# untitled.net
KiCad netlist of a schematic drawn in EAGLE
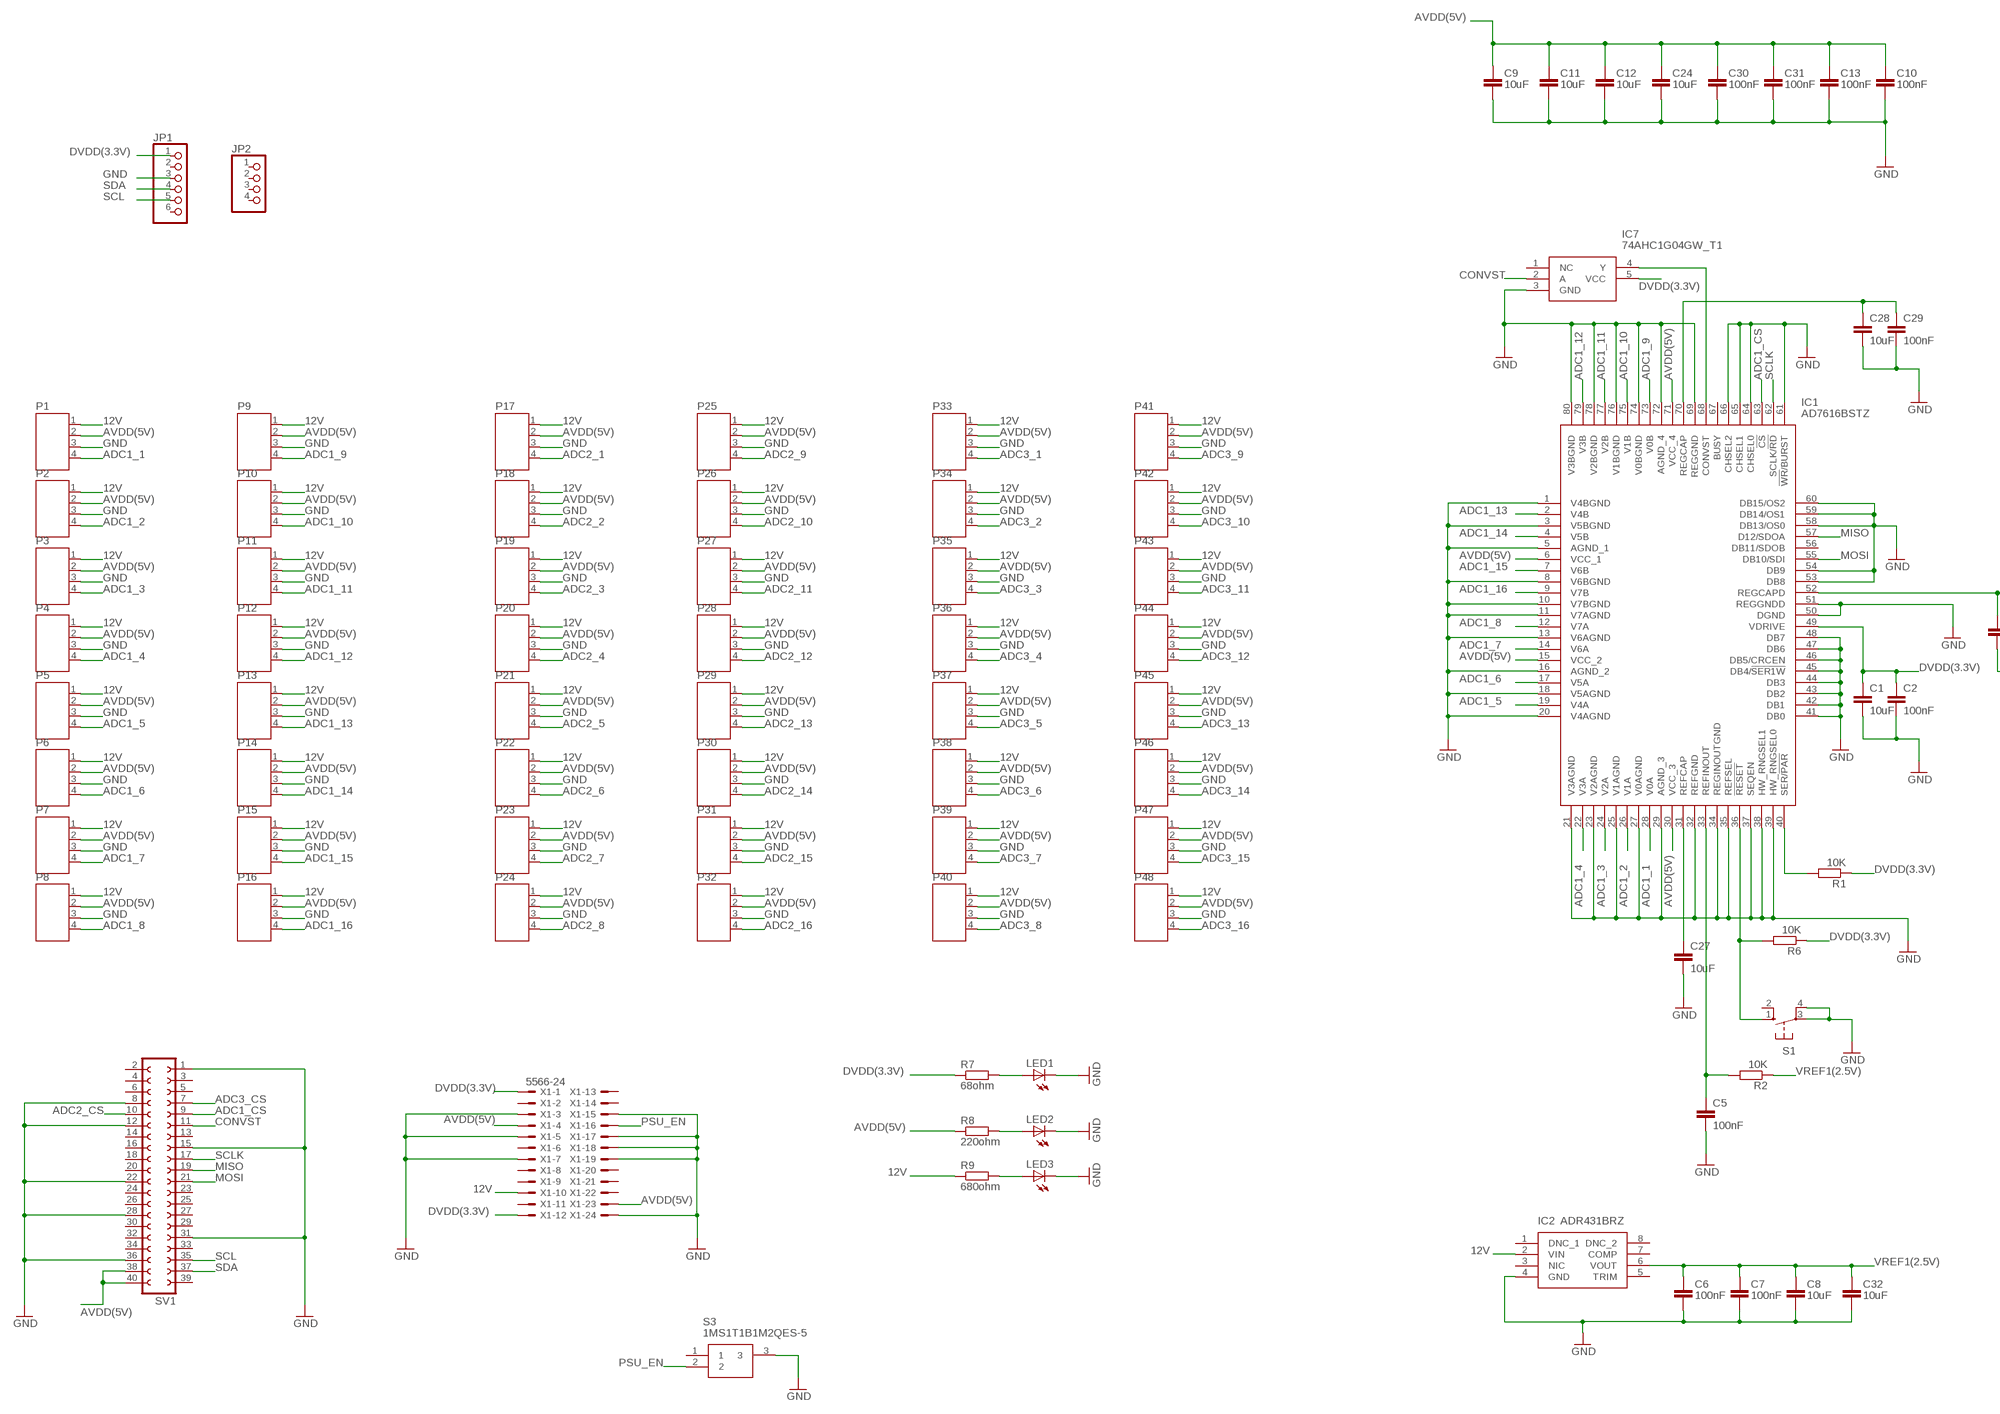
[diagram p0: schematic, sheet 1, part 1 of 2]
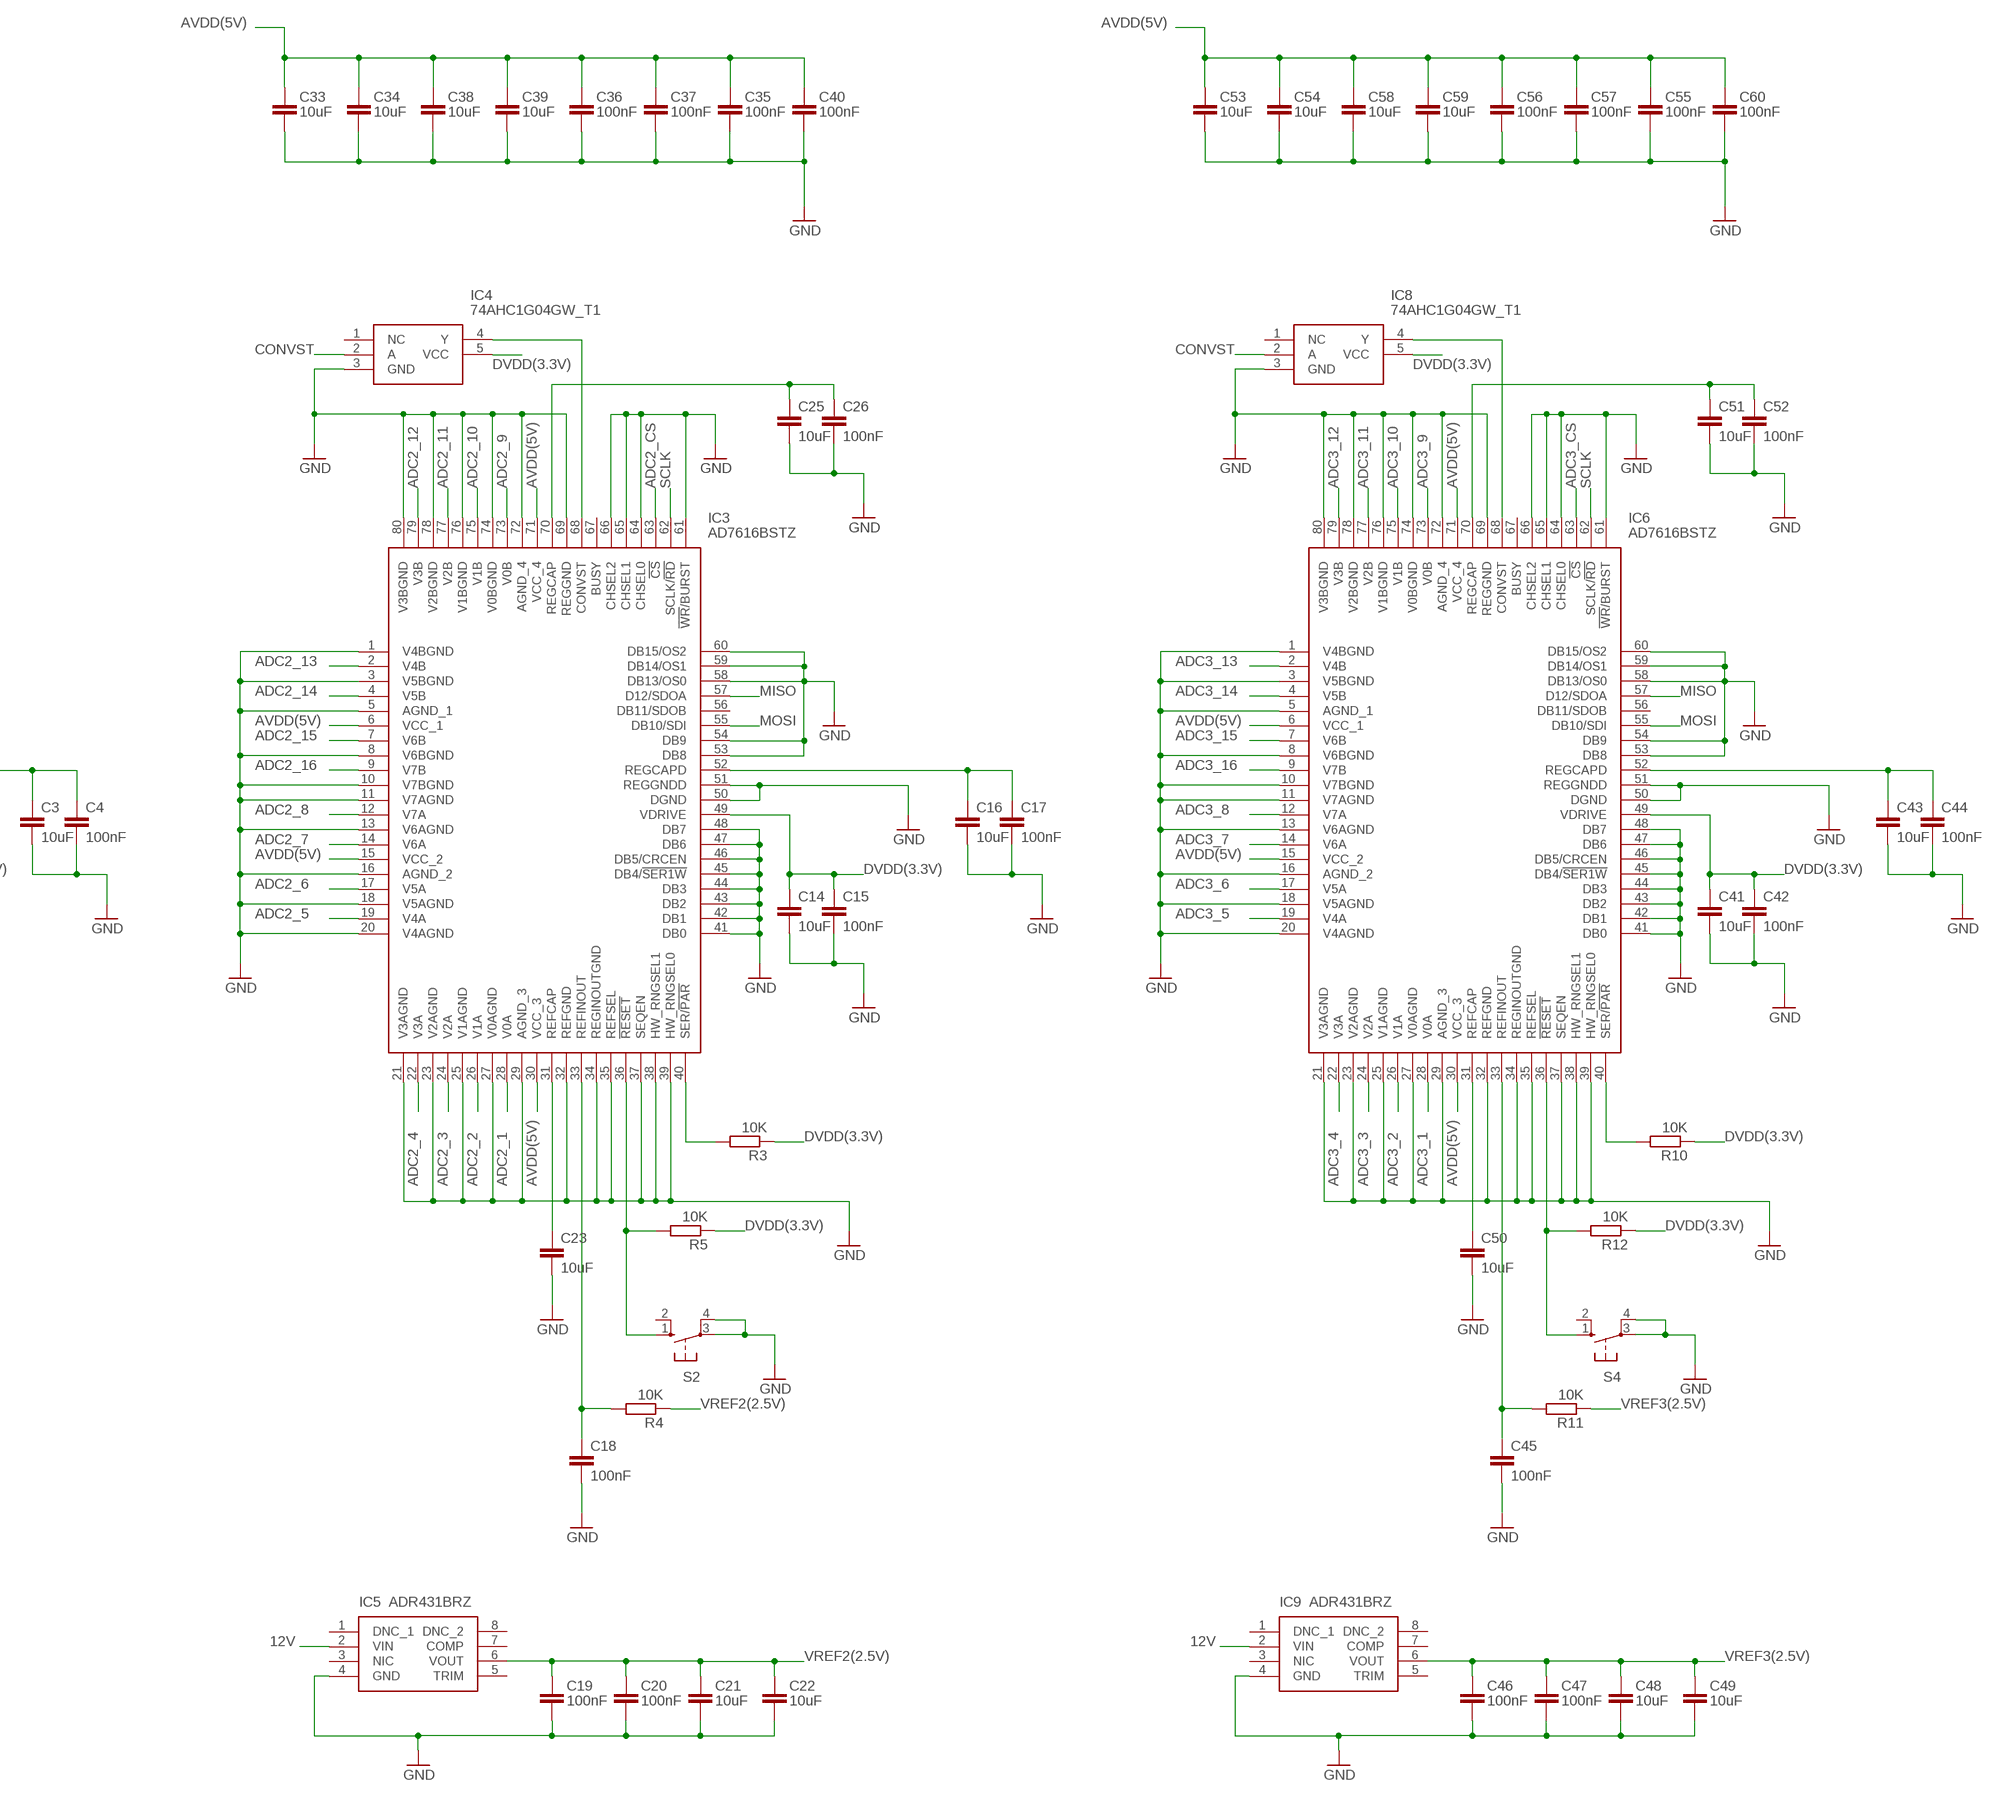
[diagram p1: schematic, sheet 1, part 2 of 2]

(export (version "E")
  (design (tool "Eeschema 10.0.6"))
  (components
    (comp (ref "C1")
      (value "10uF")
      (footprint "eagle-import:C1206")
      (libsource (lib "eagle-import") (part "C-EUC1206"))
    )
    (comp (ref "C2")
      (value "100nF")
      (footprint "eagle-import:C0603")
      (libsource (lib "eagle-import") (part "C-EUC0603"))
    )
    (comp (ref "C3")
      (value "10uF")
      (footprint "eagle-import:C1206")
      (libsource (lib "eagle-import") (part "C-EUC1206"))
    )
    (comp (ref "C4")
      (value "100nF")
      (footprint "eagle-import:C0603")
      (libsource (lib "eagle-import") (part "C-EUC0603"))
    )
    (comp (ref "C5")
      (value "100nF")
      (footprint "eagle-import:C0603")
      (libsource (lib "eagle-import") (part "C-EUC0603"))
    )
    (comp (ref "C6")
      (value "100nF")
      (footprint "eagle-import:C0603")
      (libsource (lib "eagle-import") (part "C-EUC0603"))
    )
    (comp (ref "C7")
      (value "100nF")
      (footprint "eagle-import:C0603")
      (libsource (lib "eagle-import") (part "C-EUC0603"))
    )
    (comp (ref "C8")
      (value "10uF")
      (footprint "eagle-import:C1206")
      (libsource (lib "eagle-import") (part "C-EUC1206"))
    )
    (comp (ref "C9")
      (value "10uF")
      (footprint "eagle-import:C1206")
      (libsource (lib "eagle-import") (part "C-EUC1206"))
    )
    (comp (ref "C10")
      (value "100nF")
      (footprint "eagle-import:C0603")
      (libsource (lib "eagle-import") (part "C-EUC0603"))
    )
    (comp (ref "C11")
      (value "10uF")
      (footprint "eagle-import:C1206")
      (libsource (lib "eagle-import") (part "C-EUC1206"))
    )
    (comp (ref "C12")
      (value "10uF")
      (footprint "eagle-import:C1206")
      (libsource (lib "eagle-import") (part "C-EUC1206"))
    )
    (comp (ref "C13")
      (value "100nF")
      (footprint "eagle-import:C0603")
      (libsource (lib "eagle-import") (part "C-EUC0603"))
    )
    (comp (ref "C14")
      (value "10uF")
      (footprint "eagle-import:C1206")
      (libsource (lib "eagle-import") (part "C-EUC1206"))
    )
    (comp (ref "C15")
      (value "100nF")
      (footprint "eagle-import:C0603")
      (libsource (lib "eagle-import") (part "C-EUC0603"))
    )
    (comp (ref "C16")
      (value "10uF")
      (footprint "eagle-import:C1206")
      (libsource (lib "eagle-import") (part "C-EUC1206"))
    )
    (comp (ref "C17")
      (value "100nF")
      (footprint "eagle-import:C0603")
      (libsource (lib "eagle-import") (part "C-EUC0603"))
    )
    (comp (ref "C18")
      (value "100nF")
      (footprint "eagle-import:C0603")
      (libsource (lib "eagle-import") (part "C-EUC0603"))
    )
    (comp (ref "C19")
      (value "100nF")
      (footprint "eagle-import:C0603")
      (libsource (lib "eagle-import") (part "C-EUC0603"))
    )
    (comp (ref "C20")
      (value "100nF")
      (footprint "eagle-import:C0603")
      (libsource (lib "eagle-import") (part "C-EUC0603"))
    )
    (comp (ref "C21")
      (value "10uF")
      (footprint "eagle-import:C1206")
      (libsource (lib "eagle-import") (part "C-EUC1206"))
    )
    (comp (ref "C22")
      (value "10uF")
      (footprint "eagle-import:C1206")
      (libsource (lib "eagle-import") (part "C-EUC1206"))
    )
    (comp (ref "C23")
      (value "10uF")
      (footprint "eagle-import:C1206")
      (libsource (lib "eagle-import") (part "C-EUC1206"))
    )
    (comp (ref "C24")
      (value "10uF")
      (footprint "eagle-import:C1206")
      (libsource (lib "eagle-import") (part "C-EUC1206"))
    )
    (comp (ref "C25")
      (value "10uF")
      (footprint "eagle-import:C1206")
      (libsource (lib "eagle-import") (part "C-EUC1206"))
    )
    (comp (ref "C26")
      (value "100nF")
      (footprint "eagle-import:C0603")
      (libsource (lib "eagle-import") (part "C-EUC0603"))
    )
    (comp (ref "C27")
      (value "10uF")
      (footprint "eagle-import:C1206")
      (libsource (lib "eagle-import") (part "C-EUC1206"))
    )
    (comp (ref "C28")
      (value "10uF")
      (footprint "eagle-import:C1206")
      (libsource (lib "eagle-import") (part "C-EUC1206"))
    )
    (comp (ref "C29")
      (value "100nF")
      (footprint "eagle-import:C0603")
      (libsource (lib "eagle-import") (part "C-EUC0603"))
    )
    (comp (ref "C30")
      (value "100nF")
      (footprint "eagle-import:C0603")
      (libsource (lib "eagle-import") (part "C-EUC0603"))
    )
    (comp (ref "C31")
      (value "100nF")
      (footprint "eagle-import:C0603")
      (libsource (lib "eagle-import") (part "C-EUC0603"))
    )
    (comp (ref "C32")
      (value "10uF")
      (footprint "eagle-import:C1206")
      (libsource (lib "eagle-import") (part "C-EUC1206"))
    )
    (comp (ref "C33")
      (value "10uF")
      (footprint "eagle-import:C1206")
      (libsource (lib "eagle-import") (part "C-EUC1206"))
    )
    (comp (ref "C34")
      (value "10uF")
      (footprint "eagle-import:C1206")
      (libsource (lib "eagle-import") (part "C-EUC1206"))
    )
    (comp (ref "C35")
      (value "100nF")
      (footprint "eagle-import:C0603")
      (libsource (lib "eagle-import") (part "C-EUC0603"))
    )
    (comp (ref "C36")
      (value "100nF")
      (footprint "eagle-import:C0603")
      (libsource (lib "eagle-import") (part "C-EUC0603"))
    )
    (comp (ref "C37")
      (value "100nF")
      (footprint "eagle-import:C0603")
      (libsource (lib "eagle-import") (part "C-EUC0603"))
    )
    (comp (ref "C38")
      (value "10uF")
      (footprint "eagle-import:C1206")
      (libsource (lib "eagle-import") (part "C-EUC1206"))
    )
    (comp (ref "C39")
      (value "10uF")
      (footprint "eagle-import:C1206")
      (libsource (lib "eagle-import") (part "C-EUC1206"))
    )
    (comp (ref "C40")
      (value "100nF")
      (footprint "eagle-import:C0603")
      (libsource (lib "eagle-import") (part "C-EUC0603"))
    )
    (comp (ref "C41")
      (value "10uF")
      (footprint "eagle-import:C1206")
      (libsource (lib "eagle-import") (part "C-EUC1206"))
    )
    (comp (ref "C42")
      (value "100nF")
      (footprint "eagle-import:C0603")
      (libsource (lib "eagle-import") (part "C-EUC0603"))
    )
    (comp (ref "C43")
      (value "10uF")
      (footprint "eagle-import:C1206")
      (libsource (lib "eagle-import") (part "C-EUC1206"))
    )
    (comp (ref "C44")
      (value "100nF")
      (footprint "eagle-import:C0603")
      (libsource (lib "eagle-import") (part "C-EUC0603"))
    )
    (comp (ref "C45")
      (value "100nF")
      (footprint "eagle-import:C0603")
      (libsource (lib "eagle-import") (part "C-EUC0603"))
    )
    (comp (ref "C46")
      (value "100nF")
      (footprint "eagle-import:C0603")
      (libsource (lib "eagle-import") (part "C-EUC0603"))
    )
    (comp (ref "C47")
      (value "100nF")
      (footprint "eagle-import:C0603")
      (libsource (lib "eagle-import") (part "C-EUC0603"))
    )
    (comp (ref "C48")
      (value "10uF")
      (footprint "eagle-import:C1206")
      (libsource (lib "eagle-import") (part "C-EUC1206"))
    )
    (comp (ref "C49")
      (value "10uF")
      (footprint "eagle-import:C1206")
      (libsource (lib "eagle-import") (part "C-EUC1206"))
    )
    (comp (ref "C50")
      (value "10uF")
      (footprint "eagle-import:C1206")
      (libsource (lib "eagle-import") (part "C-EUC1206"))
    )
    (comp (ref "C51")
      (value "10uF")
      (footprint "eagle-import:C1206")
      (libsource (lib "eagle-import") (part "C-EUC1206"))
    )
    (comp (ref "C52")
      (value "100nF")
      (footprint "eagle-import:C0603")
      (libsource (lib "eagle-import") (part "C-EUC0603"))
    )
    (comp (ref "C53")
      (value "10uF")
      (footprint "eagle-import:C1206")
      (libsource (lib "eagle-import") (part "C-EUC1206"))
    )
    (comp (ref "C54")
      (value "10uF")
      (footprint "eagle-import:C1206")
      (libsource (lib "eagle-import") (part "C-EUC1206"))
    )
    (comp (ref "C55")
      (value "100nF")
      (footprint "eagle-import:C0603")
      (libsource (lib "eagle-import") (part "C-EUC0603"))
    )
    (comp (ref "C56")
      (value "100nF")
      (footprint "eagle-import:C0603")
      (libsource (lib "eagle-import") (part "C-EUC0603"))
    )
    (comp (ref "C57")
      (value "100nF")
      (footprint "eagle-import:C0603")
      (libsource (lib "eagle-import") (part "C-EUC0603"))
    )
    (comp (ref "C58")
      (value "10uF")
      (footprint "eagle-import:C1206")
      (libsource (lib "eagle-import") (part "C-EUC1206"))
    )
    (comp (ref "C59")
      (value "10uF")
      (footprint "eagle-import:C1206")
      (libsource (lib "eagle-import") (part "C-EUC1206"))
    )
    (comp (ref "C60")
      (value "100nF")
      (footprint "eagle-import:C0603")
      (libsource (lib "eagle-import") (part "C-EUC0603"))
    )
    (comp (ref "IC1")
      (value "AD7616BSTZ")
      (footprint "eagle-import:QFP65P1600X1600X160-80N")
      (fields (field (name "MOUSER_PART_NUMBER") "584-AD7616BSTZ") (field (name "RS_PART_NUMBER") "1311218P"))
      (libsource (lib "eagle-import") (part "AD7616BSTZ"))
    )
    (comp (ref "IC2")
      (value "ADR431BRZ")
      (footprint "eagle-import:SOIC127P600X175-8N")
      (fields (field (name "MOUSER_PART_NUMBER") "584-ADR431BRZ") (field (name "RS_PART_NUMBER") "6977745P"))
      (libsource (lib "eagle-import") (part "ADR431BRZ"))
    )
    (comp (ref "IC3")
      (value "AD7616BSTZ")
      (footprint "eagle-import:QFP65P1600X1600X160-80N")
      (fields (field (name "MOUSER_PART_NUMBER") "584-AD7616BSTZ") (field (name "RS_PART_NUMBER") "1311218P"))
      (libsource (lib "eagle-import") (part "AD7616BSTZ"))
    )
    (comp (ref "IC4")
      (value "74AHC1G04GW_T1")
      (footprint "eagle-import:SOT65P212X110-5N")
      (fields (field (name "MANUFACTURER_PART_NUMBER") "74AHC1G04GW/T1"))
      (libsource (lib "eagle-import") (part "74AHC1G04GW_T1"))
    )
    (comp (ref "IC5")
      (value "ADR431BRZ")
      (footprint "eagle-import:SOIC127P600X175-8N")
      (fields (field (name "MOUSER_PART_NUMBER") "584-ADR431BRZ") (field (name "RS_PART_NUMBER") "6977745P"))
      (libsource (lib "eagle-import") (part "ADR431BRZ"))
    )
    (comp (ref "IC6")
      (value "AD7616BSTZ")
      (footprint "eagle-import:QFP65P1600X1600X160-80N")
      (fields (field (name "MOUSER_PART_NUMBER") "584-AD7616BSTZ") (field (name "RS_PART_NUMBER") "1311218P"))
      (libsource (lib "eagle-import") (part "AD7616BSTZ"))
    )
    (comp (ref "IC7")
      (value "74AHC1G04GW_T1")
      (footprint "eagle-import:SOT65P212X110-5N")
      (fields (field (name "MANUFACTURER_PART_NUMBER") "74AHC1G04GW/T1"))
      (libsource (lib "eagle-import") (part "74AHC1G04GW_T1"))
    )
    (comp (ref "IC8")
      (value "74AHC1G04GW_T1")
      (footprint "eagle-import:SOT65P212X110-5N")
      (fields (field (name "MANUFACTURER_PART_NUMBER") "74AHC1G04GW/T1"))
      (libsource (lib "eagle-import") (part "74AHC1G04GW_T1"))
    )
    (comp (ref "IC9")
      (value "ADR431BRZ")
      (footprint "eagle-import:SOIC127P600X175-8N")
      (fields (field (name "MOUSER_PART_NUMBER") "584-ADR431BRZ") (field (name "RS_PART_NUMBER") "6977745P"))
      (libsource (lib "eagle-import") (part "ADR431BRZ"))
    )
    (comp (ref "JP1")
      (value "PINHD-1X6")
      (footprint "eagle-import:1X06")
      (libsource (lib "eagle-import") (part "PINHD-1X6"))
    )
    (comp (ref "JP2")
      (value "PINHD-1X4")
      (footprint "eagle-import:1X04")
      (libsource (lib "eagle-import") (part "PINHD-1X4"))
    )
    (comp (ref "LED1")
      (value "LEDCHIPLED_0603")
      (footprint "eagle-import:CHIPLED_0603")
      (libsource (lib "eagle-import") (part "LEDCHIPLED_0603"))
    )
    (comp (ref "LED2")
      (value "LEDCHIPLED_0603")
      (footprint "eagle-import:CHIPLED_0603")
      (libsource (lib "eagle-import") (part "LEDCHIPLED_0603"))
    )
    (comp (ref "LED3")
      (value "LEDCHIPLED_0603")
      (footprint "eagle-import:CHIPLED_0603")
      (libsource (lib "eagle-import") (part "LEDCHIPLED_0603"))
    )
    (comp (ref "P1")
      (value "JST-PH4")
      (footprint "eagle-import:JST-PH4")
      (libsource (lib "eagle-import") (part "JST-PH4"))
    )
    (comp (ref "P2")
      (value "JST-PH4")
      (footprint "eagle-import:JST-PH4")
      (libsource (lib "eagle-import") (part "JST-PH4"))
    )
    (comp (ref "P3")
      (value "JST-PH4")
      (footprint "eagle-import:JST-PH4")
      (libsource (lib "eagle-import") (part "JST-PH4"))
    )
    (comp (ref "P4")
      (value "JST-PH4")
      (footprint "eagle-import:JST-PH4")
      (libsource (lib "eagle-import") (part "JST-PH4"))
    )
    (comp (ref "P5")
      (value "JST-PH4")
      (footprint "eagle-import:JST-PH4")
      (libsource (lib "eagle-import") (part "JST-PH4"))
    )
    (comp (ref "P6")
      (value "JST-PH4")
      (footprint "eagle-import:JST-PH4")
      (libsource (lib "eagle-import") (part "JST-PH4"))
    )
    (comp (ref "P7")
      (value "JST-PH4")
      (footprint "eagle-import:JST-PH4")
      (libsource (lib "eagle-import") (part "JST-PH4"))
    )
    (comp (ref "P8")
      (value "JST-PH4")
      (footprint "eagle-import:JST-PH4")
      (libsource (lib "eagle-import") (part "JST-PH4"))
    )
    (comp (ref "P9")
      (value "JST-PH4")
      (footprint "eagle-import:JST-PH4")
      (libsource (lib "eagle-import") (part "JST-PH4"))
    )
    (comp (ref "P10")
      (value "JST-PH4")
      (footprint "eagle-import:JST-PH4")
      (libsource (lib "eagle-import") (part "JST-PH4"))
    )
    (comp (ref "P11")
      (value "JST-PH4")
      (footprint "eagle-import:JST-PH4")
      (libsource (lib "eagle-import") (part "JST-PH4"))
    )
    (comp (ref "P12")
      (value "JST-PH4")
      (footprint "eagle-import:JST-PH4")
      (libsource (lib "eagle-import") (part "JST-PH4"))
    )
    (comp (ref "P13")
      (value "JST-PH4")
      (footprint "eagle-import:JST-PH4")
      (libsource (lib "eagle-import") (part "JST-PH4"))
    )
    (comp (ref "P14")
      (value "JST-PH4")
      (footprint "eagle-import:JST-PH4")
      (libsource (lib "eagle-import") (part "JST-PH4"))
    )
    (comp (ref "P15")
      (value "JST-PH4")
      (footprint "eagle-import:JST-PH4")
      (libsource (lib "eagle-import") (part "JST-PH4"))
    )
    (comp (ref "P16")
      (value "JST-PH4")
      (footprint "eagle-import:JST-PH4")
      (libsource (lib "eagle-import") (part "JST-PH4"))
    )
    (comp (ref "P17")
      (value "JST-PH4")
      (footprint "eagle-import:JST-PH4")
      (libsource (lib "eagle-import") (part "JST-PH4"))
    )
    (comp (ref "P18")
      (value "JST-PH4")
      (footprint "eagle-import:JST-PH4")
      (libsource (lib "eagle-import") (part "JST-PH4"))
    )
    (comp (ref "P19")
      (value "JST-PH4")
      (footprint "eagle-import:JST-PH4")
      (libsource (lib "eagle-import") (part "JST-PH4"))
    )
    (comp (ref "P20")
      (value "JST-PH4")
      (footprint "eagle-import:JST-PH4")
      (libsource (lib "eagle-import") (part "JST-PH4"))
    )
    (comp (ref "P21")
      (value "JST-PH4")
      (footprint "eagle-import:JST-PH4")
      (libsource (lib "eagle-import") (part "JST-PH4"))
    )
    (comp (ref "P22")
      (value "JST-PH4")
      (footprint "eagle-import:JST-PH4")
      (libsource (lib "eagle-import") (part "JST-PH4"))
    )
    (comp (ref "P23")
      (value "JST-PH4")
      (footprint "eagle-import:JST-PH4")
      (libsource (lib "eagle-import") (part "JST-PH4"))
    )
    (comp (ref "P24")
      (value "JST-PH4")
      (footprint "eagle-import:JST-PH4")
      (libsource (lib "eagle-import") (part "JST-PH4"))
    )
    (comp (ref "P25")
      (value "JST-PH4")
      (footprint "eagle-import:JST-PH4")
      (libsource (lib "eagle-import") (part "JST-PH4"))
    )
    (comp (ref "P26")
      (value "JST-PH4")
      (footprint "eagle-import:JST-PH4")
      (libsource (lib "eagle-import") (part "JST-PH4"))
    )
    (comp (ref "P27")
      (value "JST-PH4")
      (footprint "eagle-import:JST-PH4")
      (libsource (lib "eagle-import") (part "JST-PH4"))
    )
    (comp (ref "P28")
      (value "JST-PH4")
      (footprint "eagle-import:JST-PH4")
      (libsource (lib "eagle-import") (part "JST-PH4"))
    )
    (comp (ref "P29")
      (value "JST-PH4")
      (footprint "eagle-import:JST-PH4")
      (libsource (lib "eagle-import") (part "JST-PH4"))
    )
    (comp (ref "P30")
      (value "JST-PH4")
      (footprint "eagle-import:JST-PH4")
      (libsource (lib "eagle-import") (part "JST-PH4"))
    )
    (comp (ref "P31")
      (value "JST-PH4")
      (footprint "eagle-import:JST-PH4")
      (libsource (lib "eagle-import") (part "JST-PH4"))
    )
    (comp (ref "P32")
      (value "JST-PH4")
      (footprint "eagle-import:JST-PH4")
      (libsource (lib "eagle-import") (part "JST-PH4"))
    )
    (comp (ref "P33")
      (value "JST-PH4")
      (footprint "eagle-import:JST-PH4")
      (libsource (lib "eagle-import") (part "JST-PH4"))
    )
    (comp (ref "P34")
      (value "JST-PH4")
      (footprint "eagle-import:JST-PH4")
      (libsource (lib "eagle-import") (part "JST-PH4"))
    )
    (comp (ref "P35")
      (value "JST-PH4")
      (footprint "eagle-import:JST-PH4")
      (libsource (lib "eagle-import") (part "JST-PH4"))
    )
    (comp (ref "P36")
      (value "JST-PH4")
      (footprint "eagle-import:JST-PH4")
      (libsource (lib "eagle-import") (part "JST-PH4"))
    )
    (comp (ref "P37")
      (value "JST-PH4")
      (footprint "eagle-import:JST-PH4")
      (libsource (lib "eagle-import") (part "JST-PH4"))
    )
    (comp (ref "P38")
      (value "JST-PH4")
      (footprint "eagle-import:JST-PH4")
      (libsource (lib "eagle-import") (part "JST-PH4"))
    )
    (comp (ref "P39")
      (value "JST-PH4")
      (footprint "eagle-import:JST-PH4")
      (libsource (lib "eagle-import") (part "JST-PH4"))
    )
    (comp (ref "P40")
      (value "JST-PH4")
      (footprint "eagle-import:JST-PH4")
      (libsource (lib "eagle-import") (part "JST-PH4"))
    )
    (comp (ref "P41")
      (value "JST-PH4")
      (footprint "eagle-import:JST-PH4")
      (libsource (lib "eagle-import") (part "JST-PH4"))
    )
    (comp (ref "P42")
      (value "JST-PH4")
      (footprint "eagle-import:JST-PH4")
      (libsource (lib "eagle-import") (part "JST-PH4"))
    )
    (comp (ref "P43")
      (value "JST-PH4")
      (footprint "eagle-import:JST-PH4")
      (libsource (lib "eagle-import") (part "JST-PH4"))
    )
    (comp (ref "P44")
      (value "JST-PH4")
      (footprint "eagle-import:JST-PH4")
      (libsource (lib "eagle-import") (part "JST-PH4"))
    )
    (comp (ref "P45")
      (value "JST-PH4")
      (footprint "eagle-import:JST-PH4")
      (libsource (lib "eagle-import") (part "JST-PH4"))
    )
    (comp (ref "P46")
      (value "JST-PH4")
      (footprint "eagle-import:JST-PH4")
      (libsource (lib "eagle-import") (part "JST-PH4"))
    )
    (comp (ref "P47")
      (value "JST-PH4")
      (footprint "eagle-import:JST-PH4")
      (libsource (lib "eagle-import") (part "JST-PH4"))
    )
    (comp (ref "P48")
      (value "JST-PH4")
      (footprint "eagle-import:JST-PH4")
      (libsource (lib "eagle-import") (part "JST-PH4"))
    )
    (comp (ref "R1")
      (value "10K")
      (footprint "eagle-import:R0603")
      (libsource (lib "eagle-import") (part "R-EU_R0603"))
    )
    (comp (ref "R2")
      (value "10K")
      (footprint "eagle-import:R0603")
      (libsource (lib "eagle-import") (part "R-EU_R0603"))
    )
    (comp (ref "R3")
      (value "10K")
      (footprint "eagle-import:R0603")
      (libsource (lib "eagle-import") (part "R-EU_R0603"))
    )
    (comp (ref "R4")
      (value "10K")
      (footprint "eagle-import:R0603")
      (libsource (lib "eagle-import") (part "R-EU_R0603"))
    )
    (comp (ref "R5")
      (value "10K")
      (footprint "eagle-import:R0603")
      (libsource (lib "eagle-import") (part "R-EU_R0603"))
    )
    (comp (ref "R6")
      (value "10K")
      (footprint "eagle-import:R0603")
      (libsource (lib "eagle-import") (part "R-EU_R0603"))
    )
    (comp (ref "R7")
      (value "68ohm")
      (footprint "eagle-import:R0805")
      (libsource (lib "eagle-import") (part "R-EU_R0805"))
    )
    (comp (ref "R8")
      (value "220ohm")
      (footprint "eagle-import:R0805")
      (libsource (lib "eagle-import") (part "R-EU_R0805"))
    )
    (comp (ref "R9")
      (value "680ohm")
      (footprint "eagle-import:R0805")
      (libsource (lib "eagle-import") (part "R-EU_R0805"))
    )
    (comp (ref "R10")
      (value "10K")
      (footprint "eagle-import:R0603")
      (libsource (lib "eagle-import") (part "R-EU_R0603"))
    )
    (comp (ref "R11")
      (value "10K")
      (footprint "eagle-import:R0603")
      (libsource (lib "eagle-import") (part "R-EU_R0603"))
    )
    (comp (ref "R12")
      (value "10K")
      (footprint "eagle-import:R0603")
      (libsource (lib "eagle-import") (part "R-EU_R0603"))
    )
    (comp (ref "S1")
      (value "10-XX")
      (footprint "eagle-import:B3F-10XX")
      (fields (field (name "MPN") "B3F-1000"))
      (libsource (lib "eagle-import") (part "10-XX"))
    )
    (comp (ref "S2")
      (value "10-XX")
      (footprint "eagle-import:B3F-10XX")
      (fields (field (name "MPN") "B3F-1000"))
      (libsource (lib "eagle-import") (part "10-XX"))
    )
    (comp (ref "S3")
      (value "1MS1T1B1M2QES-5")
      (footprint "eagle-import:1MS1T1B1M2QES-5")
      (fields (field (name "RS_PART_NUMBER") "7347066"))
      (libsource (lib "eagle-import") (part "1MS1T1B1M2QES-5"))
    )
    (comp (ref "S4")
      (value "10-XX")
      (footprint "eagle-import:B3F-10XX")
      (fields (field (name "MPN") "B3F-1000"))
      (libsource (lib "eagle-import") (part "10-XX"))
    )
    (comp (ref "SV1")
      (value "FE20-2")
      (footprint "eagle-import:FE20-2")
      (libsource (lib "eagle-import") (part "FE20-2"))
    )
    (comp (ref "X1")
      (value "5566-24")
      (footprint "eagle-import:5566-24")
      (fields (field (name "MF") "MOLEX"))
      (libsource (lib "eagle-import") (part "5566-24"))
    )
  )
  (nets
    (net (code "1") (name "/12V") (class "Default")
      (node (ref "IC2") (pin "2") (pinfunction "VIN_2") (pintype "bidirectional"))
      (node (ref "IC5") (pin "2") (pinfunction "VIN_2") (pintype "bidirectional"))
      (node (ref "IC9") (pin "2") (pinfunction "VIN_2") (pintype "bidirectional"))
      (node (ref "P1") (pin "1") (pinfunction "1_1") (pintype "passive"))
      (node (ref "P10") (pin "1") (pinfunction "1_1") (pintype "passive"))
      (node (ref "P11") (pin "1") (pinfunction "1_1") (pintype "passive"))
      (node (ref "P12") (pin "1") (pinfunction "1_1") (pintype "passive"))
      (node (ref "P13") (pin "1") (pinfunction "1_1") (pintype "passive"))
      (node (ref "P14") (pin "1") (pinfunction "1_1") (pintype "passive"))
      (node (ref "P15") (pin "1") (pinfunction "1_1") (pintype "passive"))
      (node (ref "P16") (pin "1") (pinfunction "1_1") (pintype "passive"))
      (node (ref "P17") (pin "1") (pinfunction "1_1") (pintype "passive"))
      (node (ref "P18") (pin "1") (pinfunction "1_1") (pintype "passive"))
      (node (ref "P19") (pin "1") (pinfunction "1_1") (pintype "passive"))
      (node (ref "P2") (pin "1") (pinfunction "1_1") (pintype "passive"))
      (node (ref "P20") (pin "1") (pinfunction "1_1") (pintype "passive"))
      (node (ref "P21") (pin "1") (pinfunction "1_1") (pintype "passive"))
      (node (ref "P22") (pin "1") (pinfunction "1_1") (pintype "passive"))
      (node (ref "P23") (pin "1") (pinfunction "1_1") (pintype "passive"))
      (node (ref "P24") (pin "1") (pinfunction "1_1") (pintype "passive"))
      (node (ref "P25") (pin "1") (pinfunction "1_1") (pintype "passive"))
      (node (ref "P26") (pin "1") (pinfunction "1_1") (pintype "passive"))
      (node (ref "P27") (pin "1") (pinfunction "1_1") (pintype "passive"))
      (node (ref "P28") (pin "1") (pinfunction "1_1") (pintype "passive"))
      (node (ref "P29") (pin "1") (pinfunction "1_1") (pintype "passive"))
      (node (ref "P3") (pin "1") (pinfunction "1_1") (pintype "passive"))
      (node (ref "P30") (pin "1") (pinfunction "1_1") (pintype "passive"))
      (node (ref "P31") (pin "1") (pinfunction "1_1") (pintype "passive"))
      (node (ref "P32") (pin "1") (pinfunction "1_1") (pintype "passive"))
      (node (ref "P33") (pin "1") (pinfunction "1_1") (pintype "passive"))
      (node (ref "P34") (pin "1") (pinfunction "1_1") (pintype "passive"))
      (node (ref "P35") (pin "1") (pinfunction "1_1") (pintype "passive"))
      (node (ref "P36") (pin "1") (pinfunction "1_1") (pintype "passive"))
      (node (ref "P37") (pin "1") (pinfunction "1_1") (pintype "passive"))
      (node (ref "P38") (pin "1") (pinfunction "1_1") (pintype "passive"))
      (node (ref "P39") (pin "1") (pinfunction "1_1") (pintype "passive"))
      (node (ref "P4") (pin "1") (pinfunction "1_1") (pintype "passive"))
      (node (ref "P40") (pin "1") (pinfunction "1_1") (pintype "passive"))
      (node (ref "P41") (pin "1") (pinfunction "1_1") (pintype "passive"))
      (node (ref "P42") (pin "1") (pinfunction "1_1") (pintype "passive"))
      (node (ref "P43") (pin "1") (pinfunction "1_1") (pintype "passive"))
      (node (ref "P44") (pin "1") (pinfunction "1_1") (pintype "passive"))
      (node (ref "P45") (pin "1") (pinfunction "1_1") (pintype "passive"))
      (node (ref "P46") (pin "1") (pinfunction "1_1") (pintype "passive"))
      (node (ref "P47") (pin "1") (pinfunction "1_1") (pintype "passive"))
      (node (ref "P48") (pin "1") (pinfunction "1_1") (pintype "passive"))
      (node (ref "P5") (pin "1") (pinfunction "1_1") (pintype "passive"))
      (node (ref "P6") (pin "1") (pinfunction "1_1") (pintype "passive"))
      (node (ref "P7") (pin "1") (pinfunction "1_1") (pintype "passive"))
      (node (ref "P8") (pin "1") (pinfunction "1_1") (pintype "passive"))
      (node (ref "P9") (pin "1") (pinfunction "1_1") (pintype "passive"))
      (node (ref "R9") (pin "1") (pinfunction "1_1") (pintype "passive"))
      (node (ref "X1") (pin "10") (pinfunction "S_10") (pintype "passive"))
    )
    (net (code "2") (name "/ADC1_1") (class "Default")
      (node (ref "IC1") (pin "28") (pinfunction "V0A_28") (pintype "input"))
      (node (ref "P1") (pin "4") (pinfunction "4_4") (pintype "passive"))
    )
    (net (code "3") (name "/ADC1_2") (class "Default")
      (node (ref "IC1") (pin "26") (pinfunction "V1A_26") (pintype "input"))
      (node (ref "P2") (pin "4") (pinfunction "4_4") (pintype "passive"))
    )
    (net (code "4") (name "/ADC1_3") (class "Default")
      (node (ref "IC1") (pin "24") (pinfunction "V2A_24") (pintype "input"))
      (node (ref "P3") (pin "4") (pinfunction "4_4") (pintype "passive"))
    )
    (net (code "5") (name "/ADC1_4") (class "Default")
      (node (ref "IC1") (pin "22") (pinfunction "V3A_22") (pintype "input"))
      (node (ref "P4") (pin "4") (pinfunction "4_4") (pintype "passive"))
    )
    (net (code "6") (name "/ADC1_5") (class "Default")
      (node (ref "IC1") (pin "19") (pinfunction "V4A_19") (pintype "input"))
      (node (ref "P5") (pin "4") (pinfunction "4_4") (pintype "passive"))
    )
    (net (code "7") (name "/ADC1_6") (class "Default")
      (node (ref "IC1") (pin "17") (pinfunction "V5A_17") (pintype "input"))
      (node (ref "P6") (pin "4") (pinfunction "4_4") (pintype "passive"))
    )
    (net (code "8") (name "/ADC1_7") (class "Default")
      (node (ref "IC1") (pin "14") (pinfunction "V6A_14") (pintype "input"))
      (node (ref "P7") (pin "4") (pinfunction "4_4") (pintype "passive"))
    )
    (net (code "9") (name "/ADC1_8") (class "Default")
      (node (ref "IC1") (pin "12") (pinfunction "V7A_12") (pintype "input"))
      (node (ref "P8") (pin "4") (pinfunction "4_4") (pintype "passive"))
    )
    (net (code "10") (name "/ADC1_9") (class "Default")
      (node (ref "IC1") (pin "73") (pinfunction "V0B_73") (pintype "input"))
      (node (ref "P9") (pin "4") (pinfunction "4_4") (pintype "passive"))
    )
    (net (code "11") (name "/ADC1_10") (class "Default")
      (node (ref "IC1") (pin "75") (pinfunction "V1B_75") (pintype "input"))
      (node (ref "P10") (pin "4") (pinfunction "4_4") (pintype "passive"))
    )
    (net (code "12") (name "/ADC1_11") (class "Default")
      (node (ref "IC1") (pin "77") (pinfunction "V2B_77") (pintype "input"))
      (node (ref "P11") (pin "4") (pinfunction "4_4") (pintype "passive"))
    )
    (net (code "13") (name "/ADC1_12") (class "Default")
      (node (ref "IC1") (pin "79") (pinfunction "V3B_79") (pintype "input"))
      (node (ref "P12") (pin "4") (pinfunction "4_4") (pintype "passive"))
    )
    (net (code "14") (name "/ADC1_13") (class "Default")
      (node (ref "IC1") (pin "2") (pinfunction "V4B_2") (pintype "input"))
      (node (ref "P13") (pin "4") (pinfunction "4_4") (pintype "passive"))
    )
    (net (code "15") (name "/ADC1_14") (class "Default")
      (node (ref "IC1") (pin "4") (pinfunction "V5B_4") (pintype "input"))
      (node (ref "P14") (pin "4") (pinfunction "4_4") (pintype "passive"))
    )
    (net (code "16") (name "/ADC1_15") (class "Default")
      (node (ref "IC1") (pin "7") (pinfunction "V6B_7") (pintype "input"))
      (node (ref "P15") (pin "4") (pinfunction "4_4") (pintype "passive"))
    )
    (net (code "17") (name "/ADC1_16") (class "Default")
      (node (ref "IC1") (pin "9") (pinfunction "V7B_9") (pintype "input"))
      (node (ref "P16") (pin "4") (pinfunction "4_4") (pintype "passive"))
    )
    (net (code "18") (name "/ADC1_CS") (class "Default")
      (node (ref "IC1") (pin "63") (pinfunction "~{CS}_63") (pintype "input"))
      (node (ref "SV1") (pin "9") (pinfunction "9_9") (pintype "passive"))
    )
    (net (code "19") (name "/ADC2_1") (class "Default")
      (node (ref "IC3") (pin "28") (pinfunction "V0A_28") (pintype "input"))
      (node (ref "P17") (pin "4") (pinfunction "4_4") (pintype "passive"))
    )
    (net (code "20") (name "/ADC2_2") (class "Default")
      (node (ref "IC3") (pin "26") (pinfunction "V1A_26") (pintype "input"))
      (node (ref "P18") (pin "4") (pinfunction "4_4") (pintype "passive"))
    )
    (net (code "21") (name "/ADC2_3") (class "Default")
      (node (ref "IC3") (pin "24") (pinfunction "V2A_24") (pintype "input"))
      (node (ref "P19") (pin "4") (pinfunction "4_4") (pintype "passive"))
    )
    (net (code "22") (name "/ADC2_4") (class "Default")
      (node (ref "IC3") (pin "22") (pinfunction "V3A_22") (pintype "input"))
      (node (ref "P20") (pin "4") (pinfunction "4_4") (pintype "passive"))
    )
    (net (code "23") (name "/ADC2_5") (class "Default")
      (node (ref "IC3") (pin "19") (pinfunction "V4A_19") (pintype "input"))
      (node (ref "P21") (pin "4") (pinfunction "4_4") (pintype "passive"))
    )
    (net (code "24") (name "/ADC2_6") (class "Default")
      (node (ref "IC3") (pin "17") (pinfunction "V5A_17") (pintype "input"))
      (node (ref "P22") (pin "4") (pinfunction "4_4") (pintype "passive"))
    )
    (net (code "25") (name "/ADC2_7") (class "Default")
      (node (ref "IC3") (pin "14") (pinfunction "V6A_14") (pintype "input"))
      (node (ref "P23") (pin "4") (pinfunction "4_4") (pintype "passive"))
    )
    (net (code "26") (name "/ADC2_8") (class "Default")
      (node (ref "IC3") (pin "12") (pinfunction "V7A_12") (pintype "input"))
      (node (ref "P24") (pin "4") (pinfunction "4_4") (pintype "passive"))
    )
    (net (code "27") (name "/ADC2_9") (class "Default")
      (node (ref "IC3") (pin "73") (pinfunction "V0B_73") (pintype "input"))
      (node (ref "P25") (pin "4") (pinfunction "4_4") (pintype "passive"))
    )
    (net (code "28") (name "/ADC2_10") (class "Default")
      (node (ref "IC3") (pin "75") (pinfunction "V1B_75") (pintype "input"))
      (node (ref "P26") (pin "4") (pinfunction "4_4") (pintype "passive"))
    )
    (net (code "29") (name "/ADC2_11") (class "Default")
      (node (ref "IC3") (pin "77") (pinfunction "V2B_77") (pintype "input"))
      (node (ref "P27") (pin "4") (pinfunction "4_4") (pintype "passive"))
    )
    (net (code "30") (name "/ADC2_12") (class "Default")
      (node (ref "IC3") (pin "79") (pinfunction "V3B_79") (pintype "input"))
      (node (ref "P28") (pin "4") (pinfunction "4_4") (pintype "passive"))
    )
    (net (code "31") (name "/ADC2_13") (class "Default")
      (node (ref "IC3") (pin "2") (pinfunction "V4B_2") (pintype "input"))
      (node (ref "P29") (pin "4") (pinfunction "4_4") (pintype "passive"))
    )
    (net (code "32") (name "/ADC2_14") (class "Default")
      (node (ref "IC3") (pin "4") (pinfunction "V5B_4") (pintype "input"))
      (node (ref "P30") (pin "4") (pinfunction "4_4") (pintype "passive"))
    )
    (net (code "33") (name "/ADC2_15") (class "Default")
      (node (ref "IC3") (pin "7") (pinfunction "V6B_7") (pintype "input"))
      (node (ref "P31") (pin "4") (pinfunction "4_4") (pintype "passive"))
    )
    (net (code "34") (name "/ADC2_16") (class "Default")
      (node (ref "IC3") (pin "9") (pinfunction "V7B_9") (pintype "input"))
      (node (ref "P32") (pin "4") (pinfunction "4_4") (pintype "passive"))
    )
    (net (code "35") (name "/ADC2_CS") (class "Default")
      (node (ref "IC3") (pin "63") (pinfunction "~{CS}_63") (pintype "input"))
      (node (ref "SV1") (pin "10") (pinfunction "10_10") (pintype "passive"))
    )
    (net (code "36") (name "/ADC3_1") (class "Default")
      (node (ref "IC6") (pin "28") (pinfunction "V0A_28") (pintype "input"))
      (node (ref "P33") (pin "4") (pinfunction "4_4") (pintype "passive"))
    )
    (net (code "37") (name "/ADC3_2") (class "Default")
      (node (ref "IC6") (pin "26") (pinfunction "V1A_26") (pintype "input"))
      (node (ref "P34") (pin "4") (pinfunction "4_4") (pintype "passive"))
    )
    (net (code "38") (name "/ADC3_3") (class "Default")
      (node (ref "IC6") (pin "24") (pinfunction "V2A_24") (pintype "input"))
      (node (ref "P35") (pin "4") (pinfunction "4_4") (pintype "passive"))
    )
    (net (code "39") (name "/ADC3_4") (class "Default")
      (node (ref "IC6") (pin "22") (pinfunction "V3A_22") (pintype "input"))
      (node (ref "P36") (pin "4") (pinfunction "4_4") (pintype "passive"))
    )
    (net (code "40") (name "/ADC3_5") (class "Default")
      (node (ref "IC6") (pin "19") (pinfunction "V4A_19") (pintype "input"))
      (node (ref "P37") (pin "4") (pinfunction "4_4") (pintype "passive"))
    )
    (net (code "41") (name "/ADC3_6") (class "Default")
      (node (ref "IC6") (pin "17") (pinfunction "V5A_17") (pintype "input"))
      (node (ref "P38") (pin "4") (pinfunction "4_4") (pintype "passive"))
    )
    (net (code "42") (name "/ADC3_7") (class "Default")
      (node (ref "IC6") (pin "14") (pinfunction "V6A_14") (pintype "input"))
      (node (ref "P39") (pin "4") (pinfunction "4_4") (pintype "passive"))
    )
    (net (code "43") (name "/ADC3_8") (class "Default")
      (node (ref "IC6") (pin "12") (pinfunction "V7A_12") (pintype "input"))
      (node (ref "P40") (pin "4") (pinfunction "4_4") (pintype "passive"))
    )
    (net (code "44") (name "/ADC3_9") (class "Default")
      (node (ref "IC6") (pin "73") (pinfunction "V0B_73") (pintype "input"))
      (node (ref "P41") (pin "4") (pinfunction "4_4") (pintype "passive"))
    )
    (net (code "45") (name "/ADC3_10") (class "Default")
      (node (ref "IC6") (pin "75") (pinfunction "V1B_75") (pintype "input"))
      (node (ref "P42") (pin "4") (pinfunction "4_4") (pintype "passive"))
    )
    (net (code "46") (name "/ADC3_11") (class "Default")
      (node (ref "IC6") (pin "77") (pinfunction "V2B_77") (pintype "input"))
      (node (ref "P43") (pin "4") (pinfunction "4_4") (pintype "passive"))
    )
    (net (code "47") (name "/ADC3_12") (class "Default")
      (node (ref "IC6") (pin "79") (pinfunction "V3B_79") (pintype "input"))
      (node (ref "P44") (pin "4") (pinfunction "4_4") (pintype "passive"))
    )
    (net (code "48") (name "/ADC3_13") (class "Default")
      (node (ref "IC6") (pin "2") (pinfunction "V4B_2") (pintype "input"))
      (node (ref "P45") (pin "4") (pinfunction "4_4") (pintype "passive"))
    )
    (net (code "49") (name "/ADC3_14") (class "Default")
      (node (ref "IC6") (pin "4") (pinfunction "V5B_4") (pintype "input"))
      (node (ref "P46") (pin "4") (pinfunction "4_4") (pintype "passive"))
    )
    (net (code "50") (name "/ADC3_15") (class "Default")
      (node (ref "IC6") (pin "7") (pinfunction "V6B_7") (pintype "input"))
      (node (ref "P47") (pin "4") (pinfunction "4_4") (pintype "passive"))
    )
    (net (code "51") (name "/ADC3_16") (class "Default")
      (node (ref "IC6") (pin "9") (pinfunction "V7B_9") (pintype "input"))
      (node (ref "P48") (pin "4") (pinfunction "4_4") (pintype "passive"))
    )
    (net (code "52") (name "/ADC3_CS") (class "Default")
      (node (ref "IC6") (pin "63") (pinfunction "~{CS}_63") (pintype "input"))
      (node (ref "SV1") (pin "7") (pinfunction "7_7") (pintype "passive"))
    )
    (net (code "53") (name "/AVDD(5V)") (class "Default")
      (node (ref "C10") (pin "1") (pinfunction "1_1") (pintype "passive"))
      (node (ref "C11") (pin "1") (pinfunction "1_1") (pintype "passive"))
      (node (ref "C12") (pin "1") (pinfunction "1_1") (pintype "passive"))
      (node (ref "C13") (pin "1") (pinfunction "1_1") (pintype "passive"))
      (node (ref "C24") (pin "1") (pinfunction "1_1") (pintype "passive"))
      (node (ref "C30") (pin "1") (pinfunction "1_1") (pintype "passive"))
      (node (ref "C31") (pin "1") (pinfunction "1_1") (pintype "passive"))
      (node (ref "C33") (pin "1") (pinfunction "1_1") (pintype "passive"))
      (node (ref "C34") (pin "1") (pinfunction "1_1") (pintype "passive"))
      (node (ref "C35") (pin "1") (pinfunction "1_1") (pintype "passive"))
      (node (ref "C36") (pin "1") (pinfunction "1_1") (pintype "passive"))
      (node (ref "C37") (pin "1") (pinfunction "1_1") (pintype "passive"))
      (node (ref "C38") (pin "1") (pinfunction "1_1") (pintype "passive"))
      (node (ref "C39") (pin "1") (pinfunction "1_1") (pintype "passive"))
      (node (ref "C40") (pin "1") (pinfunction "1_1") (pintype "passive"))
      (node (ref "C53") (pin "1") (pinfunction "1_1") (pintype "passive"))
      (node (ref "C54") (pin "1") (pinfunction "1_1") (pintype "passive"))
      (node (ref "C55") (pin "1") (pinfunction "1_1") (pintype "passive"))
      (node (ref "C56") (pin "1") (pinfunction "1_1") (pintype "passive"))
      (node (ref "C57") (pin "1") (pinfunction "1_1") (pintype "passive"))
      (node (ref "C58") (pin "1") (pinfunction "1_1") (pintype "passive"))
      (node (ref "C59") (pin "1") (pinfunction "1_1") (pintype "passive"))
      (node (ref "C60") (pin "1") (pinfunction "1_1") (pintype "passive"))
      (node (ref "C9") (pin "1") (pinfunction "1_1") (pintype "passive"))
      (node (ref "IC1") (pin "15") (pinfunction "VCC_2_15") (pintype "power_in"))
      (node (ref "IC1") (pin "30") (pinfunction "VCC_3_30") (pintype "power_in"))
      (node (ref "IC1") (pin "6") (pinfunction "VCC_1_6") (pintype "power_in"))
      (node (ref "IC1") (pin "71") (pinfunction "VCC_4_71") (pintype "power_in"))
      (node (ref "IC3") (pin "15") (pinfunction "VCC_2_15") (pintype "power_in"))
      (node (ref "IC3") (pin "30") (pinfunction "VCC_3_30") (pintype "power_in"))
      (node (ref "IC3") (pin "6") (pinfunction "VCC_1_6") (pintype "power_in"))
      (node (ref "IC3") (pin "71") (pinfunction "VCC_4_71") (pintype "power_in"))
      (node (ref "IC6") (pin "15") (pinfunction "VCC_2_15") (pintype "power_in"))
      (node (ref "IC6") (pin "30") (pinfunction "VCC_3_30") (pintype "power_in"))
      (node (ref "IC6") (pin "6") (pinfunction "VCC_1_6") (pintype "power_in"))
      (node (ref "IC6") (pin "71") (pinfunction "VCC_4_71") (pintype "power_in"))
      (node (ref "P1") (pin "2") (pinfunction "2_2") (pintype "passive"))
      (node (ref "P10") (pin "2") (pinfunction "2_2") (pintype "passive"))
      (node (ref "P11") (pin "2") (pinfunction "2_2") (pintype "passive"))
      (node (ref "P12") (pin "2") (pinfunction "2_2") (pintype "passive"))
      (node (ref "P13") (pin "2") (pinfunction "2_2") (pintype "passive"))
      (node (ref "P14") (pin "2") (pinfunction "2_2") (pintype "passive"))
      (node (ref "P15") (pin "2") (pinfunction "2_2") (pintype "passive"))
      (node (ref "P16") (pin "2") (pinfunction "2_2") (pintype "passive"))
      (node (ref "P17") (pin "2") (pinfunction "2_2") (pintype "passive"))
      (node (ref "P18") (pin "2") (pinfunction "2_2") (pintype "passive"))
      (node (ref "P19") (pin "2") (pinfunction "2_2") (pintype "passive"))
      (node (ref "P2") (pin "2") (pinfunction "2_2") (pintype "passive"))
      (node (ref "P20") (pin "2") (pinfunction "2_2") (pintype "passive"))
      (node (ref "P21") (pin "2") (pinfunction "2_2") (pintype "passive"))
      (node (ref "P22") (pin "2") (pinfunction "2_2") (pintype "passive"))
      (node (ref "P23") (pin "2") (pinfunction "2_2") (pintype "passive"))
      (node (ref "P24") (pin "2") (pinfunction "2_2") (pintype "passive"))
      (node (ref "P25") (pin "2") (pinfunction "2_2") (pintype "passive"))
      (node (ref "P26") (pin "2") (pinfunction "2_2") (pintype "passive"))
      (node (ref "P27") (pin "2") (pinfunction "2_2") (pintype "passive"))
      (node (ref "P28") (pin "2") (pinfunction "2_2") (pintype "passive"))
      (node (ref "P29") (pin "2") (pinfunction "2_2") (pintype "passive"))
      (node (ref "P3") (pin "2") (pinfunction "2_2") (pintype "passive"))
      (node (ref "P30") (pin "2") (pinfunction "2_2") (pintype "passive"))
      (node (ref "P31") (pin "2") (pinfunction "2_2") (pintype "passive"))
      (node (ref "P32") (pin "2") (pinfunction "2_2") (pintype "passive"))
      (node (ref "P33") (pin "2") (pinfunction "2_2") (pintype "passive"))
      (node (ref "P34") (pin "2") (pinfunction "2_2") (pintype "passive"))
      (node (ref "P35") (pin "2") (pinfunction "2_2") (pintype "passive"))
      (node (ref "P36") (pin "2") (pinfunction "2_2") (pintype "passive"))
      (node (ref "P37") (pin "2") (pinfunction "2_2") (pintype "passive"))
      (node (ref "P38") (pin "2") (pinfunction "2_2") (pintype "passive"))
      (node (ref "P39") (pin "2") (pinfunction "2_2") (pintype "passive"))
      (node (ref "P4") (pin "2") (pinfunction "2_2") (pintype "passive"))
      (node (ref "P40") (pin "2") (pinfunction "2_2") (pintype "passive"))
      (node (ref "P41") (pin "2") (pinfunction "2_2") (pintype "passive"))
      (node (ref "P42") (pin "2") (pinfunction "2_2") (pintype "passive"))
      (node (ref "P43") (pin "2") (pinfunction "2_2") (pintype "passive"))
      (node (ref "P44") (pin "2") (pinfunction "2_2") (pintype "passive"))
      (node (ref "P45") (pin "2") (pinfunction "2_2") (pintype "passive"))
      (node (ref "P46") (pin "2") (pinfunction "2_2") (pintype "passive"))
      (node (ref "P47") (pin "2") (pinfunction "2_2") (pintype "passive"))
      (node (ref "P48") (pin "2") (pinfunction "2_2") (pintype "passive"))
      (node (ref "P5") (pin "2") (pinfunction "2_2") (pintype "passive"))
      (node (ref "P6") (pin "2") (pinfunction "2_2") (pintype "passive"))
      (node (ref "P7") (pin "2") (pinfunction "2_2") (pintype "passive"))
      (node (ref "P8") (pin "2") (pinfunction "2_2") (pintype "passive"))
      (node (ref "P9") (pin "2") (pinfunction "2_2") (pintype "passive"))
      (node (ref "R8") (pin "1") (pinfunction "1_1") (pintype "passive"))
      (node (ref "SV1") (pin "38") (pinfunction "38_38") (pintype "passive"))
      (node (ref "SV1") (pin "40") (pinfunction "40_40") (pintype "passive"))
      (node (ref "X1") (pin "23") (pinfunction "S_23") (pintype "passive"))
      (node (ref "X1") (pin "4") (pinfunction "S_4") (pintype "passive"))
    )
    (net (code "54") (name "/CONVST") (class "Default")
      (node (ref "IC4") (pin "2") (pinfunction "A_2") (pintype "bidirectional"))
      (node (ref "IC7") (pin "2") (pinfunction "A_2") (pintype "bidirectional"))
      (node (ref "IC8") (pin "2") (pinfunction "A_2") (pintype "bidirectional"))
      (node (ref "SV1") (pin "11") (pinfunction "11_11") (pintype "passive"))
    )
    (net (code "55") (name "/DVDD(3.3V)") (class "Default")
      (node (ref "C1") (pin "1") (pinfunction "1_1") (pintype "passive"))
      (node (ref "C14") (pin "1") (pinfunction "1_1") (pintype "passive"))
      (node (ref "C15") (pin "1") (pinfunction "1_1") (pintype "passive"))
      (node (ref "C2") (pin "1") (pinfunction "1_1") (pintype "passive"))
      (node (ref "C41") (pin "1") (pinfunction "1_1") (pintype "passive"))
      (node (ref "C42") (pin "1") (pinfunction "1_1") (pintype "passive"))
      (node (ref "IC1") (pin "49") (pinfunction "VDRIVE_49") (pintype "power_in"))
      (node (ref "IC3") (pin "49") (pinfunction "VDRIVE_49") (pintype "power_in"))
      (node (ref "IC4") (pin "5") (pinfunction "VCC_5") (pintype "power_in"))
      (node (ref "IC6") (pin "49") (pinfunction "VDRIVE_49") (pintype "power_in"))
      (node (ref "IC7") (pin "5") (pinfunction "VCC_5") (pintype "power_in"))
      (node (ref "IC8") (pin "5") (pinfunction "VCC_5") (pintype "power_in"))
      (node (ref "JP1") (pin "1") (pinfunction "1_1") (pintype "passive"))
      (node (ref "R1") (pin "1") (pinfunction "1_1") (pintype "passive"))
      (node (ref "R10") (pin "1") (pinfunction "1_1") (pintype "passive"))
      (node (ref "R12") (pin "1") (pinfunction "1_1") (pintype "passive"))
      (node (ref "R3") (pin "1") (pinfunction "1_1") (pintype "passive"))
      (node (ref "R5") (pin "1") (pinfunction "1_1") (pintype "passive"))
      (node (ref "R6") (pin "1") (pinfunction "1_1") (pintype "passive"))
      (node (ref "R7") (pin "1") (pinfunction "1_1") (pintype "passive"))
      (node (ref "X1") (pin "1") (pinfunction "S_1") (pintype "passive"))
      (node (ref "X1") (pin "12") (pinfunction "S_12") (pintype "passive"))
    )
    (net (code "56") (name "/MISO") (class "Default")
      (node (ref "IC1") (pin "57") (pinfunction "D12/SDOA_57") (pintype "bidirectional"))
      (node (ref "IC3") (pin "57") (pinfunction "D12/SDOA_57") (pintype "bidirectional"))
      (node (ref "IC6") (pin "57") (pinfunction "D12/SDOA_57") (pintype "bidirectional"))
      (node (ref "SV1") (pin "19") (pinfunction "19_19") (pintype "passive"))
    )
    (net (code "57") (name "/MOSI") (class "Default")
      (node (ref "IC1") (pin "55") (pinfunction "DB10/SDI_55") (pintype "bidirectional"))
      (node (ref "IC3") (pin "55") (pinfunction "DB10/SDI_55") (pintype "bidirectional"))
      (node (ref "IC6") (pin "55") (pinfunction "DB10/SDI_55") (pintype "bidirectional"))
      (node (ref "SV1") (pin "21") (pinfunction "21_21") (pintype "passive"))
    )
    (net (code "58") (name "/PSU_EN") (class "Default")
      (node (ref "S3") (pin "2") (pinfunction "2_2") (pintype "bidirectional"))
      (node (ref "X1") (pin "16") (pinfunction "S_16") (pintype "passive"))
    )
    (net (code "59") (name "/SCL") (class "Default")
      (node (ref "JP1") (pin "5") (pinfunction "5_5") (pintype "passive"))
      (node (ref "SV1") (pin "35") (pinfunction "35_35") (pintype "passive"))
    )
    (net (code "60") (name "/SCLK") (class "Default")
      (node (ref "IC1") (pin "62") (pinfunction "SCLK/~{RD}_62") (pintype "input"))
      (node (ref "IC3") (pin "62") (pinfunction "SCLK/~{RD}_62") (pintype "input"))
      (node (ref "IC6") (pin "62") (pinfunction "SCLK/~{RD}_62") (pintype "input"))
      (node (ref "SV1") (pin "17") (pinfunction "17_17") (pintype "passive"))
    )
    (net (code "61") (name "/SDA") (class "Default")
      (node (ref "JP1") (pin "4") (pinfunction "4_4") (pintype "passive"))
      (node (ref "SV1") (pin "37") (pinfunction "37_37") (pintype "passive"))
    )
    (net (code "62") (name "/VREF1(2.5V)") (class "Default")
      (node (ref "C32") (pin "1") (pinfunction "1_1") (pintype "passive"))
      (node (ref "C6") (pin "1") (pinfunction "1_1") (pintype "passive"))
      (node (ref "C7") (pin "1") (pinfunction "1_1") (pintype "passive"))
      (node (ref "C8") (pin "1") (pinfunction "1_1") (pintype "passive"))
      (node (ref "IC2") (pin "6") (pinfunction "VOUT_6") (pintype "bidirectional"))
      (node (ref "R2") (pin "1") (pinfunction "1_1") (pintype "passive"))
    )
    (net (code "63") (name "/VREF2(2.5V)") (class "Default")
      (node (ref "C19") (pin "1") (pinfunction "1_1") (pintype "passive"))
      (node (ref "C20") (pin "1") (pinfunction "1_1") (pintype "passive"))
      (node (ref "C21") (pin "1") (pinfunction "1_1") (pintype "passive"))
      (node (ref "C22") (pin "1") (pinfunction "1_1") (pintype "passive"))
      (node (ref "IC5") (pin "6") (pinfunction "VOUT_6") (pintype "bidirectional"))
      (node (ref "R4") (pin "1") (pinfunction "1_1") (pintype "passive"))
    )
    (net (code "64") (name "/VREF3(2.5V)") (class "Default")
      (node (ref "C46") (pin "1") (pinfunction "1_1") (pintype "passive"))
      (node (ref "C47") (pin "1") (pinfunction "1_1") (pintype "passive"))
      (node (ref "C48") (pin "1") (pinfunction "1_1") (pintype "passive"))
      (node (ref "C49") (pin "1") (pinfunction "1_1") (pintype "passive"))
      (node (ref "IC9") (pin "6") (pinfunction "VOUT_6") (pintype "bidirectional"))
      (node (ref "R11") (pin "1") (pinfunction "1_1") (pintype "passive"))
    )
    (net (code "65") (name "GND") (class "Default")
      (node (ref "C1") (pin "2") (pinfunction "2_2") (pintype "passive"))
      (node (ref "C10") (pin "2") (pinfunction "2_2") (pintype "passive"))
      (node (ref "C11") (pin "2") (pinfunction "2_2") (pintype "passive"))
      (node (ref "C12") (pin "2") (pinfunction "2_2") (pintype "passive"))
      (node (ref "C13") (pin "2") (pinfunction "2_2") (pintype "passive"))
      (node (ref "C14") (pin "2") (pinfunction "2_2") (pintype "passive"))
      (node (ref "C15") (pin "2") (pinfunction "2_2") (pintype "passive"))
      (node (ref "C16") (pin "2") (pinfunction "2_2") (pintype "passive"))
      (node (ref "C17") (pin "2") (pinfunction "2_2") (pintype "passive"))
      (node (ref "C18") (pin "2") (pinfunction "2_2") (pintype "passive"))
      (node (ref "C19") (pin "2") (pinfunction "2_2") (pintype "passive"))
      (node (ref "C2") (pin "2") (pinfunction "2_2") (pintype "passive"))
      (node (ref "C20") (pin "2") (pinfunction "2_2") (pintype "passive"))
      (node (ref "C21") (pin "2") (pinfunction "2_2") (pintype "passive"))
      (node (ref "C22") (pin "2") (pinfunction "2_2") (pintype "passive"))
      (node (ref "C23") (pin "2") (pinfunction "2_2") (pintype "passive"))
      (node (ref "C24") (pin "2") (pinfunction "2_2") (pintype "passive"))
      (node (ref "C25") (pin "2") (pinfunction "2_2") (pintype "passive"))
      (node (ref "C26") (pin "2") (pinfunction "2_2") (pintype "passive"))
      (node (ref "C27") (pin "2") (pinfunction "2_2") (pintype "passive"))
      (node (ref "C28") (pin "2") (pinfunction "2_2") (pintype "passive"))
      (node (ref "C29") (pin "2") (pinfunction "2_2") (pintype "passive"))
      (node (ref "C3") (pin "2") (pinfunction "2_2") (pintype "passive"))
      (node (ref "C30") (pin "2") (pinfunction "2_2") (pintype "passive"))
      (node (ref "C31") (pin "2") (pinfunction "2_2") (pintype "passive"))
      (node (ref "C32") (pin "2") (pinfunction "2_2") (pintype "passive"))
      (node (ref "C33") (pin "2") (pinfunction "2_2") (pintype "passive"))
      (node (ref "C34") (pin "2") (pinfunction "2_2") (pintype "passive"))
      (node (ref "C35") (pin "2") (pinfunction "2_2") (pintype "passive"))
      (node (ref "C36") (pin "2") (pinfunction "2_2") (pintype "passive"))
      (node (ref "C37") (pin "2") (pinfunction "2_2") (pintype "passive"))
      (node (ref "C38") (pin "2") (pinfunction "2_2") (pintype "passive"))
      (node (ref "C39") (pin "2") (pinfunction "2_2") (pintype "passive"))
      (node (ref "C4") (pin "2") (pinfunction "2_2") (pintype "passive"))
      (node (ref "C40") (pin "2") (pinfunction "2_2") (pintype "passive"))
      (node (ref "C41") (pin "2") (pinfunction "2_2") (pintype "passive"))
      (node (ref "C42") (pin "2") (pinfunction "2_2") (pintype "passive"))
      (node (ref "C43") (pin "2") (pinfunction "2_2") (pintype "passive"))
      (node (ref "C44") (pin "2") (pinfunction "2_2") (pintype "passive"))
      (node (ref "C45") (pin "2") (pinfunction "2_2") (pintype "passive"))
      (node (ref "C46") (pin "2") (pinfunction "2_2") (pintype "passive"))
      (node (ref "C47") (pin "2") (pinfunction "2_2") (pintype "passive"))
      (node (ref "C48") (pin "2") (pinfunction "2_2") (pintype "passive"))
      (node (ref "C49") (pin "2") (pinfunction "2_2") (pintype "passive"))
      (node (ref "C5") (pin "2") (pinfunction "2_2") (pintype "passive"))
      (node (ref "C50") (pin "2") (pinfunction "2_2") (pintype "passive"))
      (node (ref "C51") (pin "2") (pinfunction "2_2") (pintype "passive"))
      (node (ref "C52") (pin "2") (pinfunction "2_2") (pintype "passive"))
      (node (ref "C53") (pin "2") (pinfunction "2_2") (pintype "passive"))
      (node (ref "C54") (pin "2") (pinfunction "2_2") (pintype "passive"))
      (node (ref "C55") (pin "2") (pinfunction "2_2") (pintype "passive"))
      (node (ref "C56") (pin "2") (pinfunction "2_2") (pintype "passive"))
      (node (ref "C57") (pin "2") (pinfunction "2_2") (pintype "passive"))
      (node (ref "C58") (pin "2") (pinfunction "2_2") (pintype "passive"))
      (node (ref "C59") (pin "2") (pinfunction "2_2") (pintype "passive"))
      (node (ref "C6") (pin "2") (pinfunction "2_2") (pintype "passive"))
      (node (ref "C60") (pin "2") (pinfunction "2_2") (pintype "passive"))
      (node (ref "C7") (pin "2") (pinfunction "2_2") (pintype "passive"))
      (node (ref "C8") (pin "2") (pinfunction "2_2") (pintype "passive"))
      (node (ref "C9") (pin "2") (pinfunction "2_2") (pintype "passive"))
      (node (ref "IC1") (pin "1") (pinfunction "V4BGND_1") (pintype "input"))
      (node (ref "IC1") (pin "10") (pinfunction "V7BGND_10") (pintype "input"))
      (node (ref "IC1") (pin "11") (pinfunction "V7AGND_11") (pintype "input"))
      (node (ref "IC1") (pin "13") (pinfunction "V6AGND_13") (pintype "input"))
      (node (ref "IC1") (pin "16") (pinfunction "AGND_2_16") (pintype "power_in"))
      (node (ref "IC1") (pin "18") (pinfunction "V5AGND_18") (pintype "input"))
      (node (ref "IC1") (pin "20") (pinfunction "V4AGND_20") (pintype "input"))
      (node (ref "IC1") (pin "21") (pinfunction "V3AGND_21") (pintype "input"))
      (node (ref "IC1") (pin "23") (pinfunction "V2AGND_23") (pintype "input"))
      (node (ref "IC1") (pin "25") (pinfunction "V1AGND_25") (pintype "input"))
      (node (ref "IC1") (pin "27") (pinfunction "V0AGND_27") (pintype "input"))
      (node (ref "IC1") (pin "29") (pinfunction "AGND_3_29") (pintype "power_in"))
      (node (ref "IC1") (pin "3") (pinfunction "V5BGND_3") (pintype "input"))
      (node (ref "IC1") (pin "32") (pinfunction "REFGND_32") (pintype "power_in"))
      (node (ref "IC1") (pin "34") (pinfunction "REGINOUTGND_34") (pintype "power_in"))
      (node (ref "IC1") (pin "35") (pinfunction "REFSEL_35") (pintype "input"))
      (node (ref "IC1") (pin "37") (pinfunction "SEQEN_37") (pintype "input"))
      (node (ref "IC1") (pin "38") (pinfunction "HW_RNGSEL1_38") (pintype "input"))
      (node (ref "IC1") (pin "39") (pinfunction "HW_RNGSEL0_39") (pintype "input"))
      (node (ref "IC1") (pin "41") (pinfunction "DB0_41") (pintype "bidirectional"))
      (node (ref "IC1") (pin "42") (pinfunction "DB1_42") (pintype "bidirectional"))
      (node (ref "IC1") (pin "43") (pinfunction "DB2_43") (pintype "bidirectional"))
      (node (ref "IC1") (pin "44") (pinfunction "DB3_44") (pintype "bidirectional"))
      (node (ref "IC1") (pin "45") (pinfunction "DB4/~{SER1W}_45") (pintype "bidirectional"))
      (node (ref "IC1") (pin "46") (pinfunction "DB5/CRCEN_46") (pintype "bidirectional"))
      (node (ref "IC1") (pin "47") (pinfunction "DB6_47") (pintype "bidirectional"))
      (node (ref "IC1") (pin "48") (pinfunction "DB7_48") (pintype "bidirectional"))
      (node (ref "IC1") (pin "5") (pinfunction "AGND_1_5") (pintype "power_in"))
      (node (ref "IC1") (pin "50") (pinfunction "DGND_50") (pintype "power_in"))
      (node (ref "IC1") (pin "51") (pinfunction "REGGNDD_51") (pintype "power_in"))
      (node (ref "IC1") (pin "53") (pinfunction "DB8_53") (pintype "bidirectional"))
      (node (ref "IC1") (pin "54") (pinfunction "DB9_54") (pintype "bidirectional"))
      (node (ref "IC1") (pin "58") (pinfunction "DB13/OS0_58") (pintype "bidirectional"))
      (node (ref "IC1") (pin "59") (pinfunction "DB14/OS1_59") (pintype "bidirectional"))
      (node (ref "IC1") (pin "60") (pinfunction "DB15/OS2_60") (pintype "bidirectional"))
      (node (ref "IC1") (pin "61") (pinfunction "~{WR}/BURST_61") (pintype "input"))
      (node (ref "IC1") (pin "64") (pinfunction "CHSEL0_64") (pintype "input"))
      (node (ref "IC1") (pin "65") (pinfunction "CHSEL1_65") (pintype "input"))
      (node (ref "IC1") (pin "66") (pinfunction "CHSEL2_66") (pintype "input"))
      (node (ref "IC1") (pin "69") (pinfunction "REGGND_69") (pintype "power_in"))
      (node (ref "IC1") (pin "72") (pinfunction "AGND_4_72") (pintype "power_in"))
      (node (ref "IC1") (pin "74") (pinfunction "V0BGND_74") (pintype "input"))
      (node (ref "IC1") (pin "76") (pinfunction "V1BGND_76") (pintype "input"))
      (node (ref "IC1") (pin "78") (pinfunction "V2BGND_78") (pintype "input"))
      (node (ref "IC1") (pin "8") (pinfunction "V6BGND_8") (pintype "input"))
      (node (ref "IC1") (pin "80") (pinfunction "V3BGND_80") (pintype "input"))
      (node (ref "IC2") (pin "4") (pinfunction "GND_4") (pintype "bidirectional"))
      (node (ref "IC3") (pin "1") (pinfunction "V4BGND_1") (pintype "input"))
      (node (ref "IC3") (pin "10") (pinfunction "V7BGND_10") (pintype "input"))
      (node (ref "IC3") (pin "11") (pinfunction "V7AGND_11") (pintype "input"))
      (node (ref "IC3") (pin "13") (pinfunction "V6AGND_13") (pintype "input"))
      (node (ref "IC3") (pin "16") (pinfunction "AGND_2_16") (pintype "power_in"))
      (node (ref "IC3") (pin "18") (pinfunction "V5AGND_18") (pintype "input"))
      (node (ref "IC3") (pin "20") (pinfunction "V4AGND_20") (pintype "input"))
      (node (ref "IC3") (pin "21") (pinfunction "V3AGND_21") (pintype "input"))
      (node (ref "IC3") (pin "23") (pinfunction "V2AGND_23") (pintype "input"))
      (node (ref "IC3") (pin "25") (pinfunction "V1AGND_25") (pintype "input"))
      (node (ref "IC3") (pin "27") (pinfunction "V0AGND_27") (pintype "input"))
      (node (ref "IC3") (pin "29") (pinfunction "AGND_3_29") (pintype "power_in"))
      (node (ref "IC3") (pin "3") (pinfunction "V5BGND_3") (pintype "input"))
      (node (ref "IC3") (pin "32") (pinfunction "REFGND_32") (pintype "power_in"))
      (node (ref "IC3") (pin "34") (pinfunction "REGINOUTGND_34") (pintype "power_in"))
      (node (ref "IC3") (pin "35") (pinfunction "REFSEL_35") (pintype "input"))
      (node (ref "IC3") (pin "37") (pinfunction "SEQEN_37") (pintype "input"))
      (node (ref "IC3") (pin "38") (pinfunction "HW_RNGSEL1_38") (pintype "input"))
      (node (ref "IC3") (pin "39") (pinfunction "HW_RNGSEL0_39") (pintype "input"))
      (node (ref "IC3") (pin "41") (pinfunction "DB0_41") (pintype "bidirectional"))
      (node (ref "IC3") (pin "42") (pinfunction "DB1_42") (pintype "bidirectional"))
      (node (ref "IC3") (pin "43") (pinfunction "DB2_43") (pintype "bidirectional"))
      (node (ref "IC3") (pin "44") (pinfunction "DB3_44") (pintype "bidirectional"))
      (node (ref "IC3") (pin "45") (pinfunction "DB4/~{SER1W}_45") (pintype "bidirectional"))
      (node (ref "IC3") (pin "46") (pinfunction "DB5/CRCEN_46") (pintype "bidirectional"))
      (node (ref "IC3") (pin "47") (pinfunction "DB6_47") (pintype "bidirectional"))
      (node (ref "IC3") (pin "48") (pinfunction "DB7_48") (pintype "bidirectional"))
      (node (ref "IC3") (pin "5") (pinfunction "AGND_1_5") (pintype "power_in"))
      (node (ref "IC3") (pin "50") (pinfunction "DGND_50") (pintype "power_in"))
      (node (ref "IC3") (pin "51") (pinfunction "REGGNDD_51") (pintype "power_in"))
      (node (ref "IC3") (pin "53") (pinfunction "DB8_53") (pintype "bidirectional"))
      (node (ref "IC3") (pin "54") (pinfunction "DB9_54") (pintype "bidirectional"))
      (node (ref "IC3") (pin "58") (pinfunction "DB13/OS0_58") (pintype "bidirectional"))
      (node (ref "IC3") (pin "59") (pinfunction "DB14/OS1_59") (pintype "bidirectional"))
      (node (ref "IC3") (pin "60") (pinfunction "DB15/OS2_60") (pintype "bidirectional"))
      (node (ref "IC3") (pin "61") (pinfunction "~{WR}/BURST_61") (pintype "input"))
      (node (ref "IC3") (pin "64") (pinfunction "CHSEL0_64") (pintype "input"))
      (node (ref "IC3") (pin "65") (pinfunction "CHSEL1_65") (pintype "input"))
      (node (ref "IC3") (pin "66") (pinfunction "CHSEL2_66") (pintype "input"))
      (node (ref "IC3") (pin "69") (pinfunction "REGGND_69") (pintype "power_in"))
      (node (ref "IC3") (pin "72") (pinfunction "AGND_4_72") (pintype "power_in"))
      (node (ref "IC3") (pin "74") (pinfunction "V0BGND_74") (pintype "input"))
      (node (ref "IC3") (pin "76") (pinfunction "V1BGND_76") (pintype "input"))
      (node (ref "IC3") (pin "78") (pinfunction "V2BGND_78") (pintype "input"))
      (node (ref "IC3") (pin "8") (pinfunction "V6BGND_8") (pintype "input"))
      (node (ref "IC3") (pin "80") (pinfunction "V3BGND_80") (pintype "input"))
      (node (ref "IC4") (pin "3") (pinfunction "GND_3") (pintype "power_in"))
      (node (ref "IC5") (pin "4") (pinfunction "GND_4") (pintype "bidirectional"))
      (node (ref "IC6") (pin "1") (pinfunction "V4BGND_1") (pintype "input"))
      (node (ref "IC6") (pin "10") (pinfunction "V7BGND_10") (pintype "input"))
      (node (ref "IC6") (pin "11") (pinfunction "V7AGND_11") (pintype "input"))
      (node (ref "IC6") (pin "13") (pinfunction "V6AGND_13") (pintype "input"))
      (node (ref "IC6") (pin "16") (pinfunction "AGND_2_16") (pintype "power_in"))
      (node (ref "IC6") (pin "18") (pinfunction "V5AGND_18") (pintype "input"))
      (node (ref "IC6") (pin "20") (pinfunction "V4AGND_20") (pintype "input"))
      (node (ref "IC6") (pin "21") (pinfunction "V3AGND_21") (pintype "input"))
      (node (ref "IC6") (pin "23") (pinfunction "V2AGND_23") (pintype "input"))
      (node (ref "IC6") (pin "25") (pinfunction "V1AGND_25") (pintype "input"))
      (node (ref "IC6") (pin "27") (pinfunction "V0AGND_27") (pintype "input"))
      (node (ref "IC6") (pin "29") (pinfunction "AGND_3_29") (pintype "power_in"))
      (node (ref "IC6") (pin "3") (pinfunction "V5BGND_3") (pintype "input"))
      (node (ref "IC6") (pin "32") (pinfunction "REFGND_32") (pintype "power_in"))
      (node (ref "IC6") (pin "34") (pinfunction "REGINOUTGND_34") (pintype "power_in"))
      (node (ref "IC6") (pin "35") (pinfunction "REFSEL_35") (pintype "input"))
      (node (ref "IC6") (pin "37") (pinfunction "SEQEN_37") (pintype "input"))
      (node (ref "IC6") (pin "38") (pinfunction "HW_RNGSEL1_38") (pintype "input"))
      (node (ref "IC6") (pin "39") (pinfunction "HW_RNGSEL0_39") (pintype "input"))
      (node (ref "IC6") (pin "41") (pinfunction "DB0_41") (pintype "bidirectional"))
      (node (ref "IC6") (pin "42") (pinfunction "DB1_42") (pintype "bidirectional"))
      (node (ref "IC6") (pin "43") (pinfunction "DB2_43") (pintype "bidirectional"))
      (node (ref "IC6") (pin "44") (pinfunction "DB3_44") (pintype "bidirectional"))
      (node (ref "IC6") (pin "45") (pinfunction "DB4/~{SER1W}_45") (pintype "bidirectional"))
      (node (ref "IC6") (pin "46") (pinfunction "DB5/CRCEN_46") (pintype "bidirectional"))
      (node (ref "IC6") (pin "47") (pinfunction "DB6_47") (pintype "bidirectional"))
      (node (ref "IC6") (pin "48") (pinfunction "DB7_48") (pintype "bidirectional"))
      (node (ref "IC6") (pin "5") (pinfunction "AGND_1_5") (pintype "power_in"))
      (node (ref "IC6") (pin "50") (pinfunction "DGND_50") (pintype "power_in"))
      (node (ref "IC6") (pin "51") (pinfunction "REGGNDD_51") (pintype "power_in"))
      (node (ref "IC6") (pin "53") (pinfunction "DB8_53") (pintype "bidirectional"))
      (node (ref "IC6") (pin "54") (pinfunction "DB9_54") (pintype "bidirectional"))
      (node (ref "IC6") (pin "58") (pinfunction "DB13/OS0_58") (pintype "bidirectional"))
      (node (ref "IC6") (pin "59") (pinfunction "DB14/OS1_59") (pintype "bidirectional"))
      (node (ref "IC6") (pin "60") (pinfunction "DB15/OS2_60") (pintype "bidirectional"))
      (node (ref "IC6") (pin "61") (pinfunction "~{WR}/BURST_61") (pintype "input"))
      (node (ref "IC6") (pin "64") (pinfunction "CHSEL0_64") (pintype "input"))
      (node (ref "IC6") (pin "65") (pinfunction "CHSEL1_65") (pintype "input"))
      (node (ref "IC6") (pin "66") (pinfunction "CHSEL2_66") (pintype "input"))
      (node (ref "IC6") (pin "69") (pinfunction "REGGND_69") (pintype "power_in"))
      (node (ref "IC6") (pin "72") (pinfunction "AGND_4_72") (pintype "power_in"))
      (node (ref "IC6") (pin "74") (pinfunction "V0BGND_74") (pintype "input"))
      (node (ref "IC6") (pin "76") (pinfunction "V1BGND_76") (pintype "input"))
      (node (ref "IC6") (pin "78") (pinfunction "V2BGND_78") (pintype "input"))
      (node (ref "IC6") (pin "8") (pinfunction "V6BGND_8") (pintype "input"))
      (node (ref "IC6") (pin "80") (pinfunction "V3BGND_80") (pintype "input"))
      (node (ref "IC7") (pin "3") (pinfunction "GND_3") (pintype "power_in"))
      (node (ref "IC8") (pin "3") (pinfunction "GND_3") (pintype "power_in"))
      (node (ref "IC9") (pin "4") (pinfunction "GND_4") (pintype "bidirectional"))
      (node (ref "JP1") (pin "3") (pinfunction "3_3") (pintype "passive"))
      (node (ref "LED1") (pin "C") (pinfunction "C_C") (pintype "passive"))
      (node (ref "LED2") (pin "C") (pinfunction "C_C") (pintype "passive"))
      (node (ref "LED3") (pin "C") (pinfunction "C_C") (pintype "passive"))
      (node (ref "P1") (pin "3") (pinfunction "3_3") (pintype "passive"))
      (node (ref "P10") (pin "3") (pinfunction "3_3") (pintype "passive"))
      (node (ref "P11") (pin "3") (pinfunction "3_3") (pintype "passive"))
      (node (ref "P12") (pin "3") (pinfunction "3_3") (pintype "passive"))
      (node (ref "P13") (pin "3") (pinfunction "3_3") (pintype "passive"))
      (node (ref "P14") (pin "3") (pinfunction "3_3") (pintype "passive"))
      (node (ref "P15") (pin "3") (pinfunction "3_3") (pintype "passive"))
      (node (ref "P16") (pin "3") (pinfunction "3_3") (pintype "passive"))
      (node (ref "P17") (pin "3") (pinfunction "3_3") (pintype "passive"))
      (node (ref "P18") (pin "3") (pinfunction "3_3") (pintype "passive"))
      (node (ref "P19") (pin "3") (pinfunction "3_3") (pintype "passive"))
      (node (ref "P2") (pin "3") (pinfunction "3_3") (pintype "passive"))
      (node (ref "P20") (pin "3") (pinfunction "3_3") (pintype "passive"))
      (node (ref "P21") (pin "3") (pinfunction "3_3") (pintype "passive"))
      (node (ref "P22") (pin "3") (pinfunction "3_3") (pintype "passive"))
      (node (ref "P23") (pin "3") (pinfunction "3_3") (pintype "passive"))
      (node (ref "P24") (pin "3") (pinfunction "3_3") (pintype "passive"))
      (node (ref "P25") (pin "3") (pinfunction "3_3") (pintype "passive"))
      (node (ref "P26") (pin "3") (pinfunction "3_3") (pintype "passive"))
      (node (ref "P27") (pin "3") (pinfunction "3_3") (pintype "passive"))
      (node (ref "P28") (pin "3") (pinfunction "3_3") (pintype "passive"))
      (node (ref "P29") (pin "3") (pinfunction "3_3") (pintype "passive"))
      (node (ref "P3") (pin "3") (pinfunction "3_3") (pintype "passive"))
      (node (ref "P30") (pin "3") (pinfunction "3_3") (pintype "passive"))
      (node (ref "P31") (pin "3") (pinfunction "3_3") (pintype "passive"))
      (node (ref "P32") (pin "3") (pinfunction "3_3") (pintype "passive"))
      (node (ref "P33") (pin "3") (pinfunction "3_3") (pintype "passive"))
      (node (ref "P34") (pin "3") (pinfunction "3_3") (pintype "passive"))
      (node (ref "P35") (pin "3") (pinfunction "3_3") (pintype "passive"))
      (node (ref "P36") (pin "3") (pinfunction "3_3") (pintype "passive"))
      (node (ref "P37") (pin "3") (pinfunction "3_3") (pintype "passive"))
      (node (ref "P38") (pin "3") (pinfunction "3_3") (pintype "passive"))
      (node (ref "P39") (pin "3") (pinfunction "3_3") (pintype "passive"))
      (node (ref "P4") (pin "3") (pinfunction "3_3") (pintype "passive"))
      (node (ref "P40") (pin "3") (pinfunction "3_3") (pintype "passive"))
      (node (ref "P41") (pin "3") (pinfunction "3_3") (pintype "passive"))
      (node (ref "P42") (pin "3") (pinfunction "3_3") (pintype "passive"))
      (node (ref "P43") (pin "3") (pinfunction "3_3") (pintype "passive"))
      (node (ref "P44") (pin "3") (pinfunction "3_3") (pintype "passive"))
      (node (ref "P45") (pin "3") (pinfunction "3_3") (pintype "passive"))
      (node (ref "P46") (pin "3") (pinfunction "3_3") (pintype "passive"))
      (node (ref "P47") (pin "3") (pinfunction "3_3") (pintype "passive"))
      (node (ref "P48") (pin "3") (pinfunction "3_3") (pintype "passive"))
      (node (ref "P5") (pin "3") (pinfunction "3_3") (pintype "passive"))
      (node (ref "P6") (pin "3") (pinfunction "3_3") (pintype "passive"))
      (node (ref "P7") (pin "3") (pinfunction "3_3") (pintype "passive"))
      (node (ref "P8") (pin "3") (pinfunction "3_3") (pintype "passive"))
      (node (ref "P9") (pin "3") (pinfunction "3_3") (pintype "passive"))
      (node (ref "S1") (pin "3") (pinfunction "P_3") (pintype "passive"))
      (node (ref "S1") (pin "4") (pinfunction "P1_4") (pintype "passive"))
      (node (ref "S2") (pin "3") (pinfunction "P_3") (pintype "passive"))
      (node (ref "S2") (pin "4") (pinfunction "P1_4") (pintype "passive"))
      (node (ref "S3") (pin "3") (pinfunction "3_3") (pintype "bidirectional"))
      (node (ref "S4") (pin "3") (pinfunction "P_3") (pintype "passive"))
      (node (ref "S4") (pin "4") (pinfunction "P1_4") (pintype "passive"))
      (node (ref "SV1") (pin "1") (pinfunction "1_1") (pintype "passive"))
      (node (ref "SV1") (pin "12") (pinfunction "12_12") (pintype "passive"))
      (node (ref "SV1") (pin "15") (pinfunction "15_15") (pintype "passive"))
      (node (ref "SV1") (pin "22") (pinfunction "22_22") (pintype "passive"))
      (node (ref "SV1") (pin "28") (pinfunction "28_28") (pintype "passive"))
      (node (ref "SV1") (pin "31") (pinfunction "31_31") (pintype "passive"))
      (node (ref "SV1") (pin "36") (pinfunction "36_36") (pintype "passive"))
      (node (ref "SV1") (pin "8") (pinfunction "8_8") (pintype "passive"))
      (node (ref "X1") (pin "15") (pinfunction "S_15") (pintype "passive"))
      (node (ref "X1") (pin "17") (pinfunction "S_17") (pintype "passive"))
      (node (ref "X1") (pin "18") (pinfunction "S_18") (pintype "passive"))
      (node (ref "X1") (pin "19") (pinfunction "S_19") (pintype "passive"))
      (node (ref "X1") (pin "24") (pinfunction "S_24") (pintype "passive"))
      (node (ref "X1") (pin "3") (pinfunction "S_3") (pintype "passive"))
      (node (ref "X1") (pin "5") (pinfunction "S_5") (pintype "passive"))
      (node (ref "X1") (pin "7") (pinfunction "S_7") (pintype "passive"))
    )
    (net (code "66") (name "Net-(IC1-CONVST)") (class "Default")
      (node (ref "IC1") (pin "68") (pinfunction "CONVST_68") (pintype "input"))
      (node (ref "IC7") (pin "4") (pinfunction "Y_4") (pintype "bidirectional"))
    )
    (net (code "67") (name "Net-(IC1-REFCAP)") (class "Default")
      (node (ref "C27") (pin "1") (pinfunction "1_1") (pintype "passive"))
      (node (ref "IC1") (pin "31") (pinfunction "REFCAP_31") (pintype "bidirectional"))
    )
    (net (code "68") (name "Net-(IC1-REFINOUT)") (class "Default")
      (node (ref "C5") (pin "1") (pinfunction "1_1") (pintype "passive"))
      (node (ref "IC1") (pin "33") (pinfunction "REFINOUT_33") (pintype "bidirectional"))
      (node (ref "R2") (pin "2") (pinfunction "2_2") (pintype "passive"))
    )
    (net (code "69") (name "Net-(IC1-REGCAP)") (class "Default")
      (node (ref "C28") (pin "1") (pinfunction "1_1") (pintype "passive"))
      (node (ref "C29") (pin "1") (pinfunction "1_1") (pintype "passive"))
      (node (ref "IC1") (pin "70") (pinfunction "REGCAP_70") (pintype "bidirectional"))
    )
    (net (code "70") (name "Net-(IC1-REGCAPD)") (class "Default")
      (node (ref "C3") (pin "1") (pinfunction "1_1") (pintype "passive"))
      (node (ref "C4") (pin "1") (pinfunction "1_1") (pintype "passive"))
      (node (ref "IC1") (pin "52") (pinfunction "REGCAPD_52") (pintype "bidirectional"))
    )
    (net (code "71") (name "Net-(IC1-SER{slash}~{PAR})") (class "Default")
      (node (ref "IC1") (pin "40") (pinfunction "SER/~{PAR}_40") (pintype "input"))
      (node (ref "R1") (pin "2") (pinfunction "2_2") (pintype "passive"))
    )
    (net (code "72") (name "Net-(IC1-~{RESET})") (class "Default")
      (node (ref "IC1") (pin "36") (pinfunction "~{RESET}_36") (pintype "input"))
      (node (ref "R6") (pin "2") (pinfunction "2_2") (pintype "passive"))
      (node (ref "S1") (pin "1") (pinfunction "S_1") (pintype "passive"))
    )
    (net (code "73") (name "Net-(IC3-CONVST)") (class "Default")
      (node (ref "IC3") (pin "68") (pinfunction "CONVST_68") (pintype "input"))
      (node (ref "IC4") (pin "4") (pinfunction "Y_4") (pintype "bidirectional"))
    )
    (net (code "74") (name "Net-(IC3-REFCAP)") (class "Default")
      (node (ref "C23") (pin "1") (pinfunction "1_1") (pintype "passive"))
      (node (ref "IC3") (pin "31") (pinfunction "REFCAP_31") (pintype "bidirectional"))
    )
    (net (code "75") (name "Net-(IC3-REFINOUT)") (class "Default")
      (node (ref "C18") (pin "1") (pinfunction "1_1") (pintype "passive"))
      (node (ref "IC3") (pin "33") (pinfunction "REFINOUT_33") (pintype "bidirectional"))
      (node (ref "R4") (pin "2") (pinfunction "2_2") (pintype "passive"))
    )
    (net (code "76") (name "Net-(IC3-REGCAP)") (class "Default")
      (node (ref "C25") (pin "1") (pinfunction "1_1") (pintype "passive"))
      (node (ref "C26") (pin "1") (pinfunction "1_1") (pintype "passive"))
      (node (ref "IC3") (pin "70") (pinfunction "REGCAP_70") (pintype "bidirectional"))
    )
    (net (code "77") (name "Net-(IC3-REGCAPD)") (class "Default")
      (node (ref "C16") (pin "1") (pinfunction "1_1") (pintype "passive"))
      (node (ref "C17") (pin "1") (pinfunction "1_1") (pintype "passive"))
      (node (ref "IC3") (pin "52") (pinfunction "REGCAPD_52") (pintype "bidirectional"))
    )
    (net (code "78") (name "Net-(IC3-SER{slash}~{PAR})") (class "Default")
      (node (ref "IC3") (pin "40") (pinfunction "SER/~{PAR}_40") (pintype "input"))
      (node (ref "R3") (pin "2") (pinfunction "2_2") (pintype "passive"))
    )
    (net (code "79") (name "Net-(IC3-~{RESET})") (class "Default")
      (node (ref "IC3") (pin "36") (pinfunction "~{RESET}_36") (pintype "input"))
      (node (ref "R5") (pin "2") (pinfunction "2_2") (pintype "passive"))
      (node (ref "S2") (pin "1") (pinfunction "S_1") (pintype "passive"))
    )
    (net (code "80") (name "Net-(IC6-CONVST)") (class "Default")
      (node (ref "IC6") (pin "68") (pinfunction "CONVST_68") (pintype "input"))
      (node (ref "IC8") (pin "4") (pinfunction "Y_4") (pintype "bidirectional"))
    )
    (net (code "81") (name "Net-(IC6-REFCAP)") (class "Default")
      (node (ref "C50") (pin "1") (pinfunction "1_1") (pintype "passive"))
      (node (ref "IC6") (pin "31") (pinfunction "REFCAP_31") (pintype "bidirectional"))
    )
    (net (code "82") (name "Net-(IC6-REFINOUT)") (class "Default")
      (node (ref "C45") (pin "1") (pinfunction "1_1") (pintype "passive"))
      (node (ref "IC6") (pin "33") (pinfunction "REFINOUT_33") (pintype "bidirectional"))
      (node (ref "R11") (pin "2") (pinfunction "2_2") (pintype "passive"))
    )
    (net (code "83") (name "Net-(IC6-REGCAP)") (class "Default")
      (node (ref "C51") (pin "1") (pinfunction "1_1") (pintype "passive"))
      (node (ref "C52") (pin "1") (pinfunction "1_1") (pintype "passive"))
      (node (ref "IC6") (pin "70") (pinfunction "REGCAP_70") (pintype "bidirectional"))
    )
    (net (code "84") (name "Net-(IC6-REGCAPD)") (class "Default")
      (node (ref "C43") (pin "1") (pinfunction "1_1") (pintype "passive"))
      (node (ref "C44") (pin "1") (pinfunction "1_1") (pintype "passive"))
      (node (ref "IC6") (pin "52") (pinfunction "REGCAPD_52") (pintype "bidirectional"))
    )
    (net (code "85") (name "Net-(IC6-SER{slash}~{PAR})") (class "Default")
      (node (ref "IC6") (pin "40") (pinfunction "SER/~{PAR}_40") (pintype "input"))
      (node (ref "R10") (pin "2") (pinfunction "2_2") (pintype "passive"))
    )
    (net (code "86") (name "Net-(IC6-~{RESET})") (class "Default")
      (node (ref "IC6") (pin "36") (pinfunction "~{RESET}_36") (pintype "input"))
      (node (ref "R12") (pin "2") (pinfunction "2_2") (pintype "passive"))
      (node (ref "S4") (pin "1") (pinfunction "S_1") (pintype "passive"))
    )
    (net (code "87") (name "Net-(LED1-PadA)") (class "Default")
      (node (ref "LED1") (pin "A") (pinfunction "A_A") (pintype "passive"))
      (node (ref "R7") (pin "2") (pinfunction "2_2") (pintype "passive"))
    )
    (net (code "88") (name "Net-(LED2-PadA)") (class "Default")
      (node (ref "LED2") (pin "A") (pinfunction "A_A") (pintype "passive"))
      (node (ref "R8") (pin "2") (pinfunction "2_2") (pintype "passive"))
    )
    (net (code "89") (name "Net-(LED3-PadA)") (class "Default")
      (node (ref "LED3") (pin "A") (pinfunction "A_A") (pintype "passive"))
      (node (ref "R9") (pin "2") (pinfunction "2_2") (pintype "passive"))
    )
    (net (code "90") (name "unconnected-(IC1-BUSY-Pad67)") (class "Default")
      (node (ref "IC1") (pin "67") (pinfunction "BUSY_67") (pintype "output"))
    )
    (net (code "91") (name "unconnected-(IC1-DB11{slash}SDOB-Pad56)") (class "Default")
      (node (ref "IC1") (pin "56") (pinfunction "DB11/SDOB_56") (pintype "bidirectional"))
    )
    (net (code "92") (name "unconnected-(IC2-COMP-Pad7)") (class "Default")
      (node (ref "IC2") (pin "7") (pinfunction "COMP_7") (pintype "bidirectional"))
    )
    (net (code "93") (name "unconnected-(IC2-DNC_1-Pad1)") (class "Default")
      (node (ref "IC2") (pin "1") (pinfunction "DNC_1_1") (pintype "bidirectional"))
    )
    (net (code "94") (name "unconnected-(IC2-DNC_2-Pad8)") (class "Default")
      (node (ref "IC2") (pin "8") (pinfunction "DNC_2_8") (pintype "bidirectional"))
    )
    (net (code "95") (name "unconnected-(IC2-NIC-Pad3)") (class "Default")
      (node (ref "IC2") (pin "3") (pinfunction "NIC_3") (pintype "bidirectional"))
    )
    (net (code "96") (name "unconnected-(IC2-TRIM-Pad5)") (class "Default")
      (node (ref "IC2") (pin "5") (pinfunction "TRIM_5") (pintype "bidirectional"))
    )
    (net (code "97") (name "unconnected-(IC3-BUSY-Pad67)") (class "Default")
      (node (ref "IC3") (pin "67") (pinfunction "BUSY_67") (pintype "output"))
    )
    (net (code "98") (name "unconnected-(IC3-DB11{slash}SDOB-Pad56)") (class "Default")
      (node (ref "IC3") (pin "56") (pinfunction "DB11/SDOB_56") (pintype "bidirectional"))
    )
    (net (code "99") (name "unconnected-(IC4-NC-Pad1)") (class "Default")
      (node (ref "IC4") (pin "1") (pinfunction "NC_1") (pintype "no_connect"))
    )
    (net (code "100") (name "unconnected-(IC5-COMP-Pad7)") (class "Default")
      (node (ref "IC5") (pin "7") (pinfunction "COMP_7") (pintype "bidirectional"))
    )
    (net (code "101") (name "unconnected-(IC5-DNC_1-Pad1)") (class "Default")
      (node (ref "IC5") (pin "1") (pinfunction "DNC_1_1") (pintype "bidirectional"))
    )
    (net (code "102") (name "unconnected-(IC5-DNC_2-Pad8)") (class "Default")
      (node (ref "IC5") (pin "8") (pinfunction "DNC_2_8") (pintype "bidirectional"))
    )
    (net (code "103") (name "unconnected-(IC5-NIC-Pad3)") (class "Default")
      (node (ref "IC5") (pin "3") (pinfunction "NIC_3") (pintype "bidirectional"))
    )
    (net (code "104") (name "unconnected-(IC5-TRIM-Pad5)") (class "Default")
      (node (ref "IC5") (pin "5") (pinfunction "TRIM_5") (pintype "bidirectional"))
    )
    (net (code "105") (name "unconnected-(IC6-BUSY-Pad67)") (class "Default")
      (node (ref "IC6") (pin "67") (pinfunction "BUSY_67") (pintype "output"))
    )
    (net (code "106") (name "unconnected-(IC6-DB11{slash}SDOB-Pad56)") (class "Default")
      (node (ref "IC6") (pin "56") (pinfunction "DB11/SDOB_56") (pintype "bidirectional"))
    )
    (net (code "107") (name "unconnected-(IC7-NC-Pad1)") (class "Default")
      (node (ref "IC7") (pin "1") (pinfunction "NC_1") (pintype "no_connect"))
    )
    (net (code "108") (name "unconnected-(IC8-NC-Pad1)") (class "Default")
      (node (ref "IC8") (pin "1") (pinfunction "NC_1") (pintype "no_connect"))
    )
    (net (code "109") (name "unconnected-(IC9-COMP-Pad7)") (class "Default")
      (node (ref "IC9") (pin "7") (pinfunction "COMP_7") (pintype "bidirectional"))
    )
    (net (code "110") (name "unconnected-(IC9-DNC_1-Pad1)") (class "Default")
      (node (ref "IC9") (pin "1") (pinfunction "DNC_1_1") (pintype "bidirectional"))
    )
    (net (code "111") (name "unconnected-(IC9-DNC_2-Pad8)") (class "Default")
      (node (ref "IC9") (pin "8") (pinfunction "DNC_2_8") (pintype "bidirectional"))
    )
    (net (code "112") (name "unconnected-(IC9-NIC-Pad3)") (class "Default")
      (node (ref "IC9") (pin "3") (pinfunction "NIC_3") (pintype "bidirectional"))
    )
    (net (code "113") (name "unconnected-(IC9-TRIM-Pad5)") (class "Default")
      (node (ref "IC9") (pin "5") (pinfunction "TRIM_5") (pintype "bidirectional"))
    )
    (net (code "114") (name "unconnected-(JP1-Pad2)") (class "Default")
      (node (ref "JP1") (pin "2") (pinfunction "2_2") (pintype "passive"))
    )
    (net (code "115") (name "unconnected-(JP1-Pad6)") (class "Default")
      (node (ref "JP1") (pin "6") (pinfunction "6_6") (pintype "passive"))
    )
    (net (code "116") (name "unconnected-(JP2-Pad1)") (class "Default")
      (node (ref "JP2") (pin "1") (pinfunction "1_1") (pintype "passive"))
    )
    (net (code "117") (name "unconnected-(JP2-Pad2)") (class "Default")
      (node (ref "JP2") (pin "2") (pinfunction "2_2") (pintype "passive"))
    )
    (net (code "118") (name "unconnected-(JP2-Pad3)") (class "Default")
      (node (ref "JP2") (pin "3") (pinfunction "3_3") (pintype "passive"))
    )
    (net (code "119") (name "unconnected-(JP2-Pad4)") (class "Default")
      (node (ref "JP2") (pin "4") (pinfunction "4_4") (pintype "passive"))
    )
    (net (code "120") (name "unconnected-(S1-S1-Pad2)") (class "Default")
      (node (ref "S1") (pin "2") (pinfunction "S1_2") (pintype "passive"))
    )
    (net (code "121") (name "unconnected-(S2-S1-Pad2)") (class "Default")
      (node (ref "S2") (pin "2") (pinfunction "S1_2") (pintype "passive"))
    )
    (net (code "122") (name "unconnected-(S3-Pad1)") (class "Default")
      (node (ref "S3") (pin "1") (pinfunction "1_1") (pintype "bidirectional"))
    )
    (net (code "123") (name "unconnected-(S4-S1-Pad2)") (class "Default")
      (node (ref "S4") (pin "2") (pinfunction "S1_2") (pintype "passive"))
    )
    (net (code "124") (name "unconnected-(SV1-Pad2)") (class "Default")
      (node (ref "SV1") (pin "2") (pinfunction "2_2") (pintype "passive"))
    )
    (net (code "125") (name "unconnected-(SV1-Pad3)") (class "Default")
      (node (ref "SV1") (pin "3") (pinfunction "3_3") (pintype "passive"))
    )
    (net (code "126") (name "unconnected-(SV1-Pad4)") (class "Default")
      (node (ref "SV1") (pin "4") (pinfunction "4_4") (pintype "passive"))
    )
    (net (code "127") (name "unconnected-(SV1-Pad5)") (class "Default")
      (node (ref "SV1") (pin "5") (pinfunction "5_5") (pintype "passive"))
    )
    (net (code "128") (name "unconnected-(SV1-Pad6)") (class "Default")
      (node (ref "SV1") (pin "6") (pinfunction "6_6") (pintype "passive"))
    )
    (net (code "129") (name "unconnected-(SV1-Pad13)") (class "Default")
      (node (ref "SV1") (pin "13") (pinfunction "13_13") (pintype "passive"))
    )
    (net (code "130") (name "unconnected-(SV1-Pad14)") (class "Default")
      (node (ref "SV1") (pin "14") (pinfunction "14_14") (pintype "passive"))
    )
    (net (code "131") (name "unconnected-(SV1-Pad16)") (class "Default")
      (node (ref "SV1") (pin "16") (pinfunction "16_16") (pintype "passive"))
    )
    (net (code "132") (name "unconnected-(SV1-Pad18)") (class "Default")
      (node (ref "SV1") (pin "18") (pinfunction "18_18") (pintype "passive"))
    )
    (net (code "133") (name "unconnected-(SV1-Pad20)") (class "Default")
      (node (ref "SV1") (pin "20") (pinfunction "20_20") (pintype "passive"))
    )
    (net (code "134") (name "unconnected-(SV1-Pad23)") (class "Default")
      (node (ref "SV1") (pin "23") (pinfunction "23_23") (pintype "passive"))
    )
    (net (code "135") (name "unconnected-(SV1-Pad24)") (class "Default")
      (node (ref "SV1") (pin "24") (pinfunction "24_24") (pintype "passive"))
    )
    (net (code "136") (name "unconnected-(SV1-Pad25)") (class "Default")
      (node (ref "SV1") (pin "25") (pinfunction "25_25") (pintype "passive"))
    )
    (net (code "137") (name "unconnected-(SV1-Pad26)") (class "Default")
      (node (ref "SV1") (pin "26") (pinfunction "26_26") (pintype "passive"))
    )
    (net (code "138") (name "unconnected-(SV1-Pad27)") (class "Default")
      (node (ref "SV1") (pin "27") (pinfunction "27_27") (pintype "passive"))
    )
    (net (code "139") (name "unconnected-(SV1-Pad29)") (class "Default")
      (node (ref "SV1") (pin "29") (pinfunction "29_29") (pintype "passive"))
    )
    (net (code "140") (name "unconnected-(SV1-Pad30)") (class "Default")
      (node (ref "SV1") (pin "30") (pinfunction "30_30") (pintype "passive"))
    )
    (net (code "141") (name "unconnected-(SV1-Pad32)") (class "Default")
      (node (ref "SV1") (pin "32") (pinfunction "32_32") (pintype "passive"))
    )
    (net (code "142") (name "unconnected-(SV1-Pad33)") (class "Default")
      (node (ref "SV1") (pin "33") (pinfunction "33_33") (pintype "passive"))
    )
    (net (code "143") (name "unconnected-(SV1-Pad34)") (class "Default")
      (node (ref "SV1") (pin "34") (pinfunction "34_34") (pintype "passive"))
    )
    (net (code "144") (name "unconnected-(SV1-Pad39)") (class "Default")
      (node (ref "SV1") (pin "39") (pinfunction "39_39") (pintype "passive"))
    )
    (net (code "145") (name "unconnected-(X1C-S-Pad11)") (class "Default")
      (node (ref "X1") (pin "11") (pinfunction "S_11") (pintype "passive"))
    )
    (net (code "146") (name "unconnected-(X1E-S-Pad13)") (class "Default")
      (node (ref "X1") (pin "13") (pinfunction "S_13") (pintype "passive"))
    )
    (net (code "147") (name "unconnected-(X1F-S-Pad14)") (class "Default")
      (node (ref "X1") (pin "14") (pinfunction "S_14") (pintype "passive"))
    )
    (net (code "148") (name "unconnected-(X1L-S-Pad2)") (class "Default")
      (node (ref "X1") (pin "2") (pinfunction "S_2") (pintype "passive"))
    )
    (net (code "149") (name "unconnected-(X1M-S-Pad20)") (class "Default")
      (node (ref "X1") (pin "20") (pinfunction "S_20") (pintype "passive"))
    )
    (net (code "150") (name "unconnected-(X1N-S-Pad21)") (class "Default")
      (node (ref "X1") (pin "21") (pinfunction "S_21") (pintype "passive"))
    )
    (net (code "151") (name "unconnected-(X1O-S-Pad22)") (class "Default")
      (node (ref "X1") (pin "22") (pinfunction "S_22") (pintype "passive"))
    )
    (net (code "152") (name "unconnected-(X1U-S-Pad6)") (class "Default")
      (node (ref "X1") (pin "6") (pinfunction "S_6") (pintype "passive"))
    )
    (net (code "153") (name "unconnected-(X1W-S-Pad8)") (class "Default")
      (node (ref "X1") (pin "8") (pinfunction "S_8") (pintype "passive"))
    )
    (net (code "154") (name "unconnected-(X1X-S-Pad9)") (class "Default")
      (node (ref "X1") (pin "9") (pinfunction "S_9") (pintype "passive"))
    )
  )
)
